# MN42_v2base.net
KiCad netlist of a schematic drawn in EasyEDA Pro
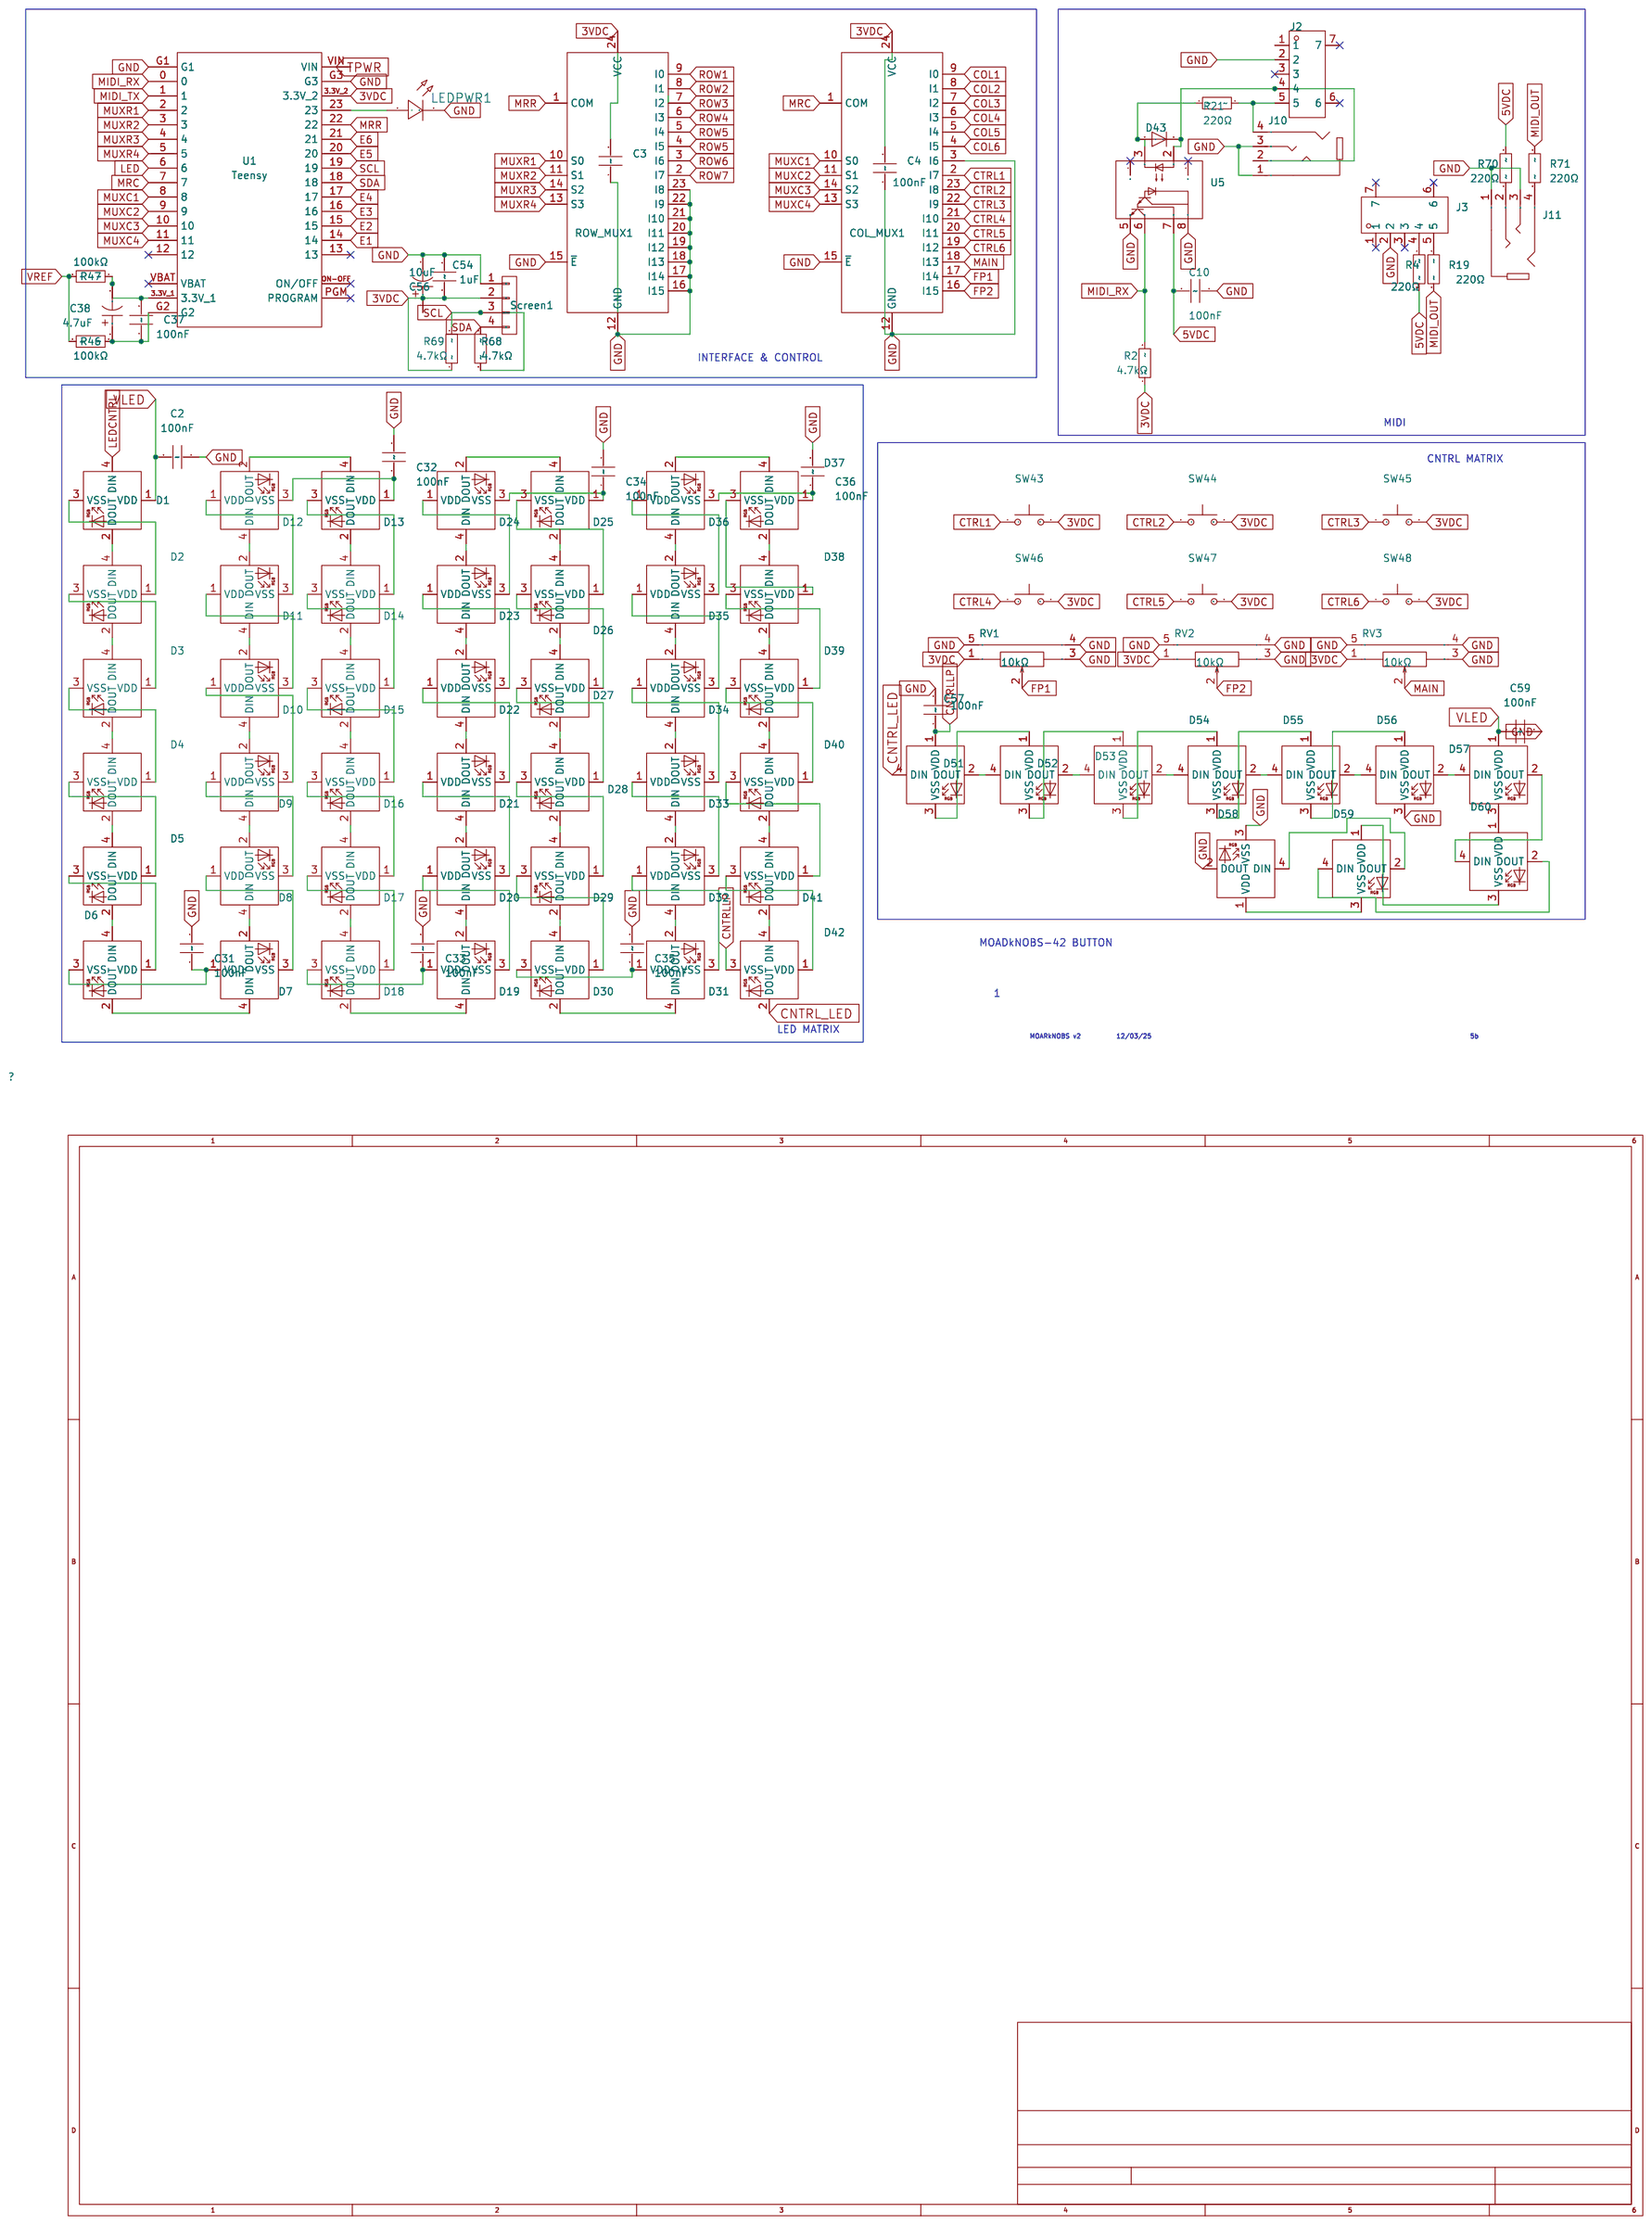
[diagram p0: INTERFACE/LED/MIDI/CNTRL]
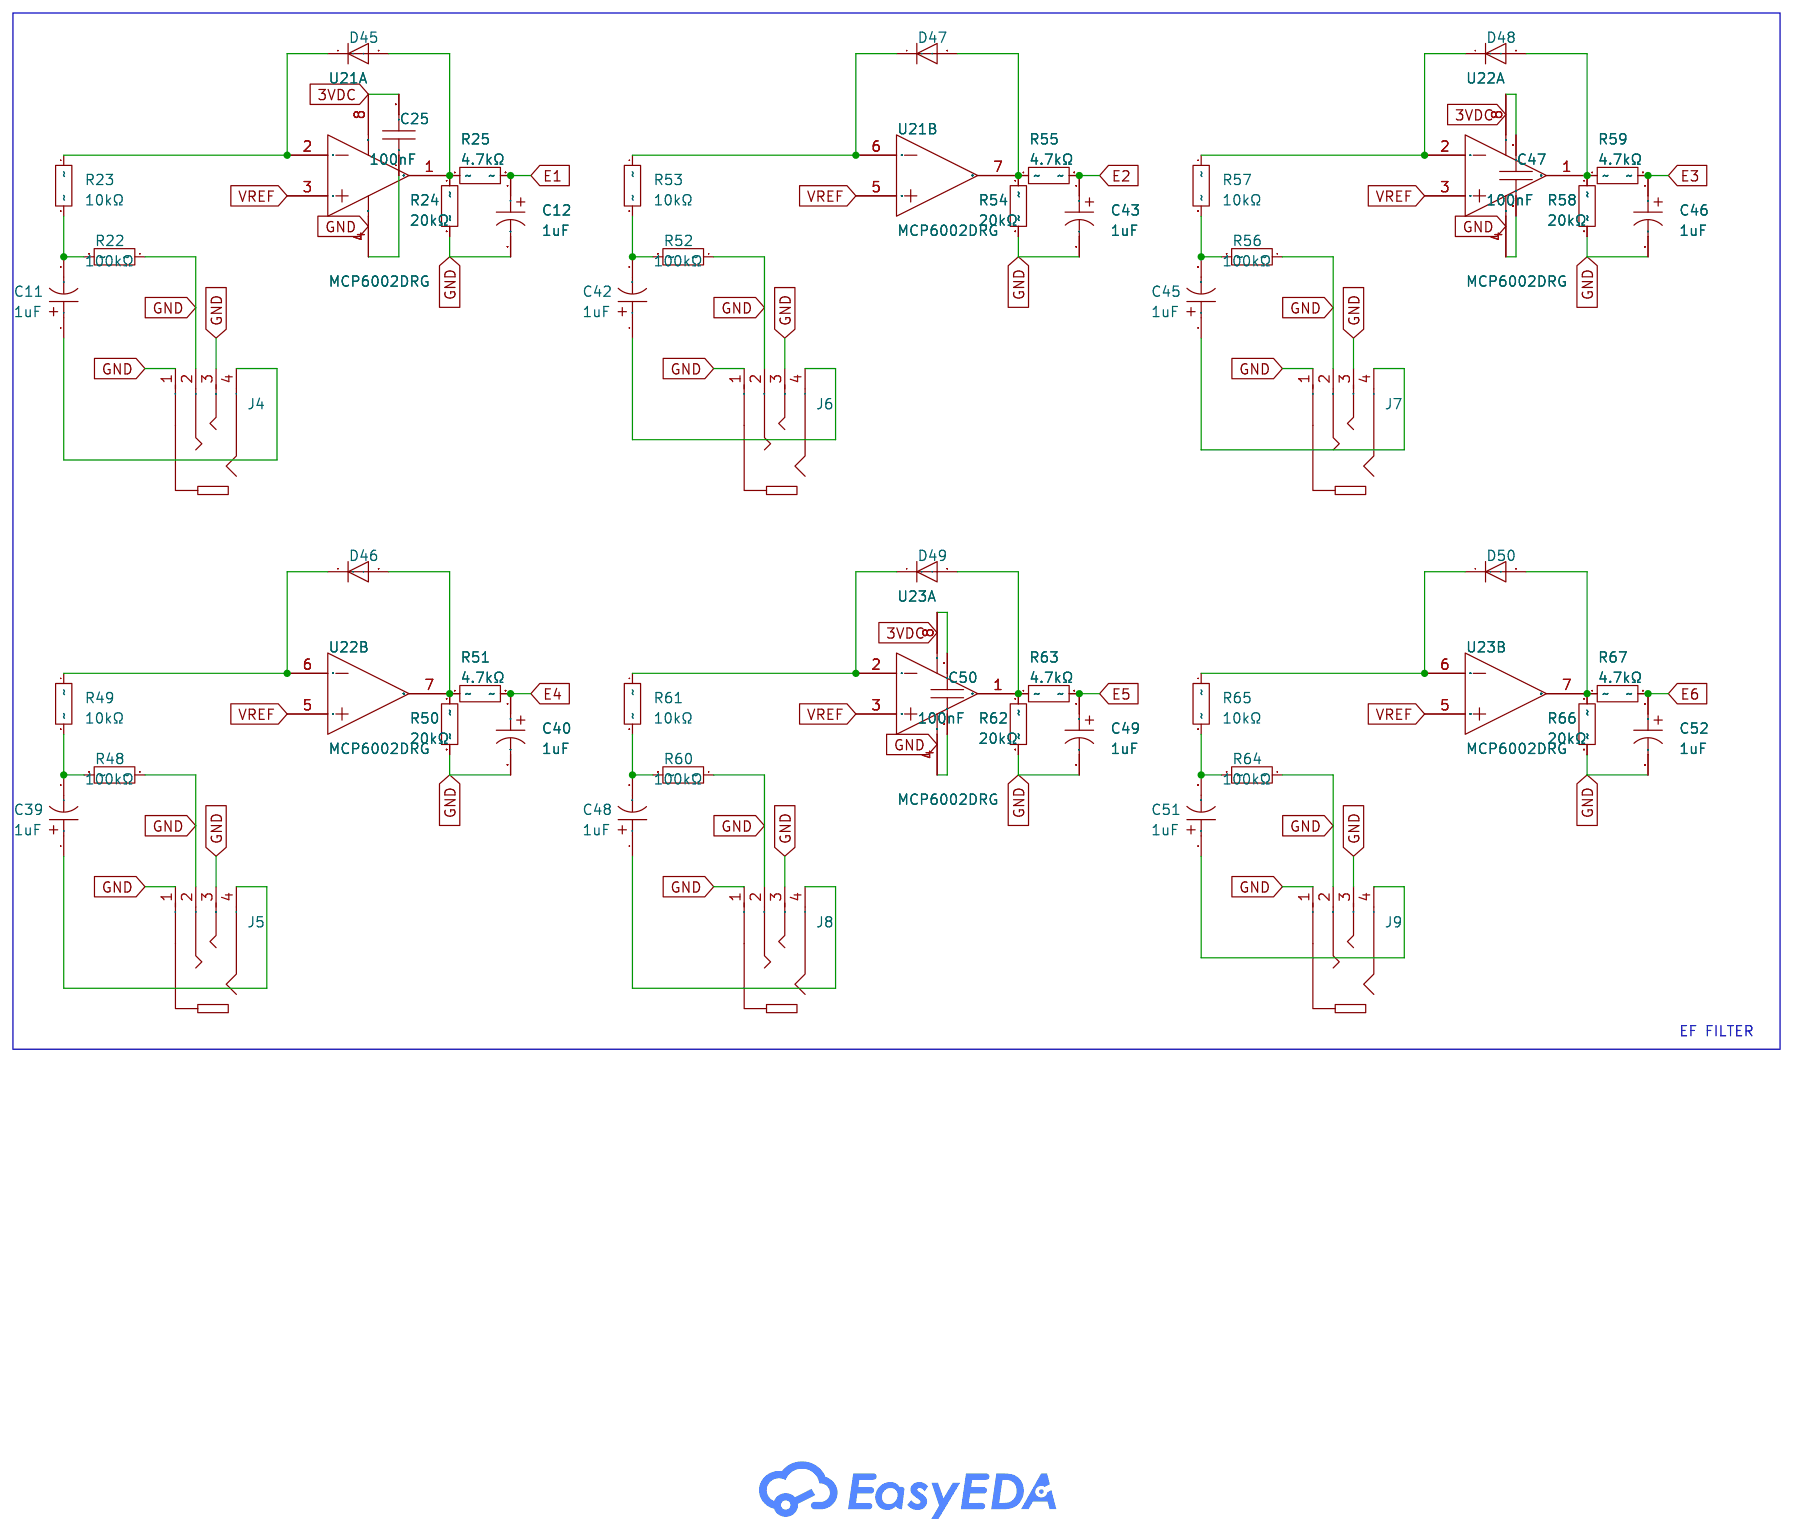
[diagram p1: ENVELOPE]
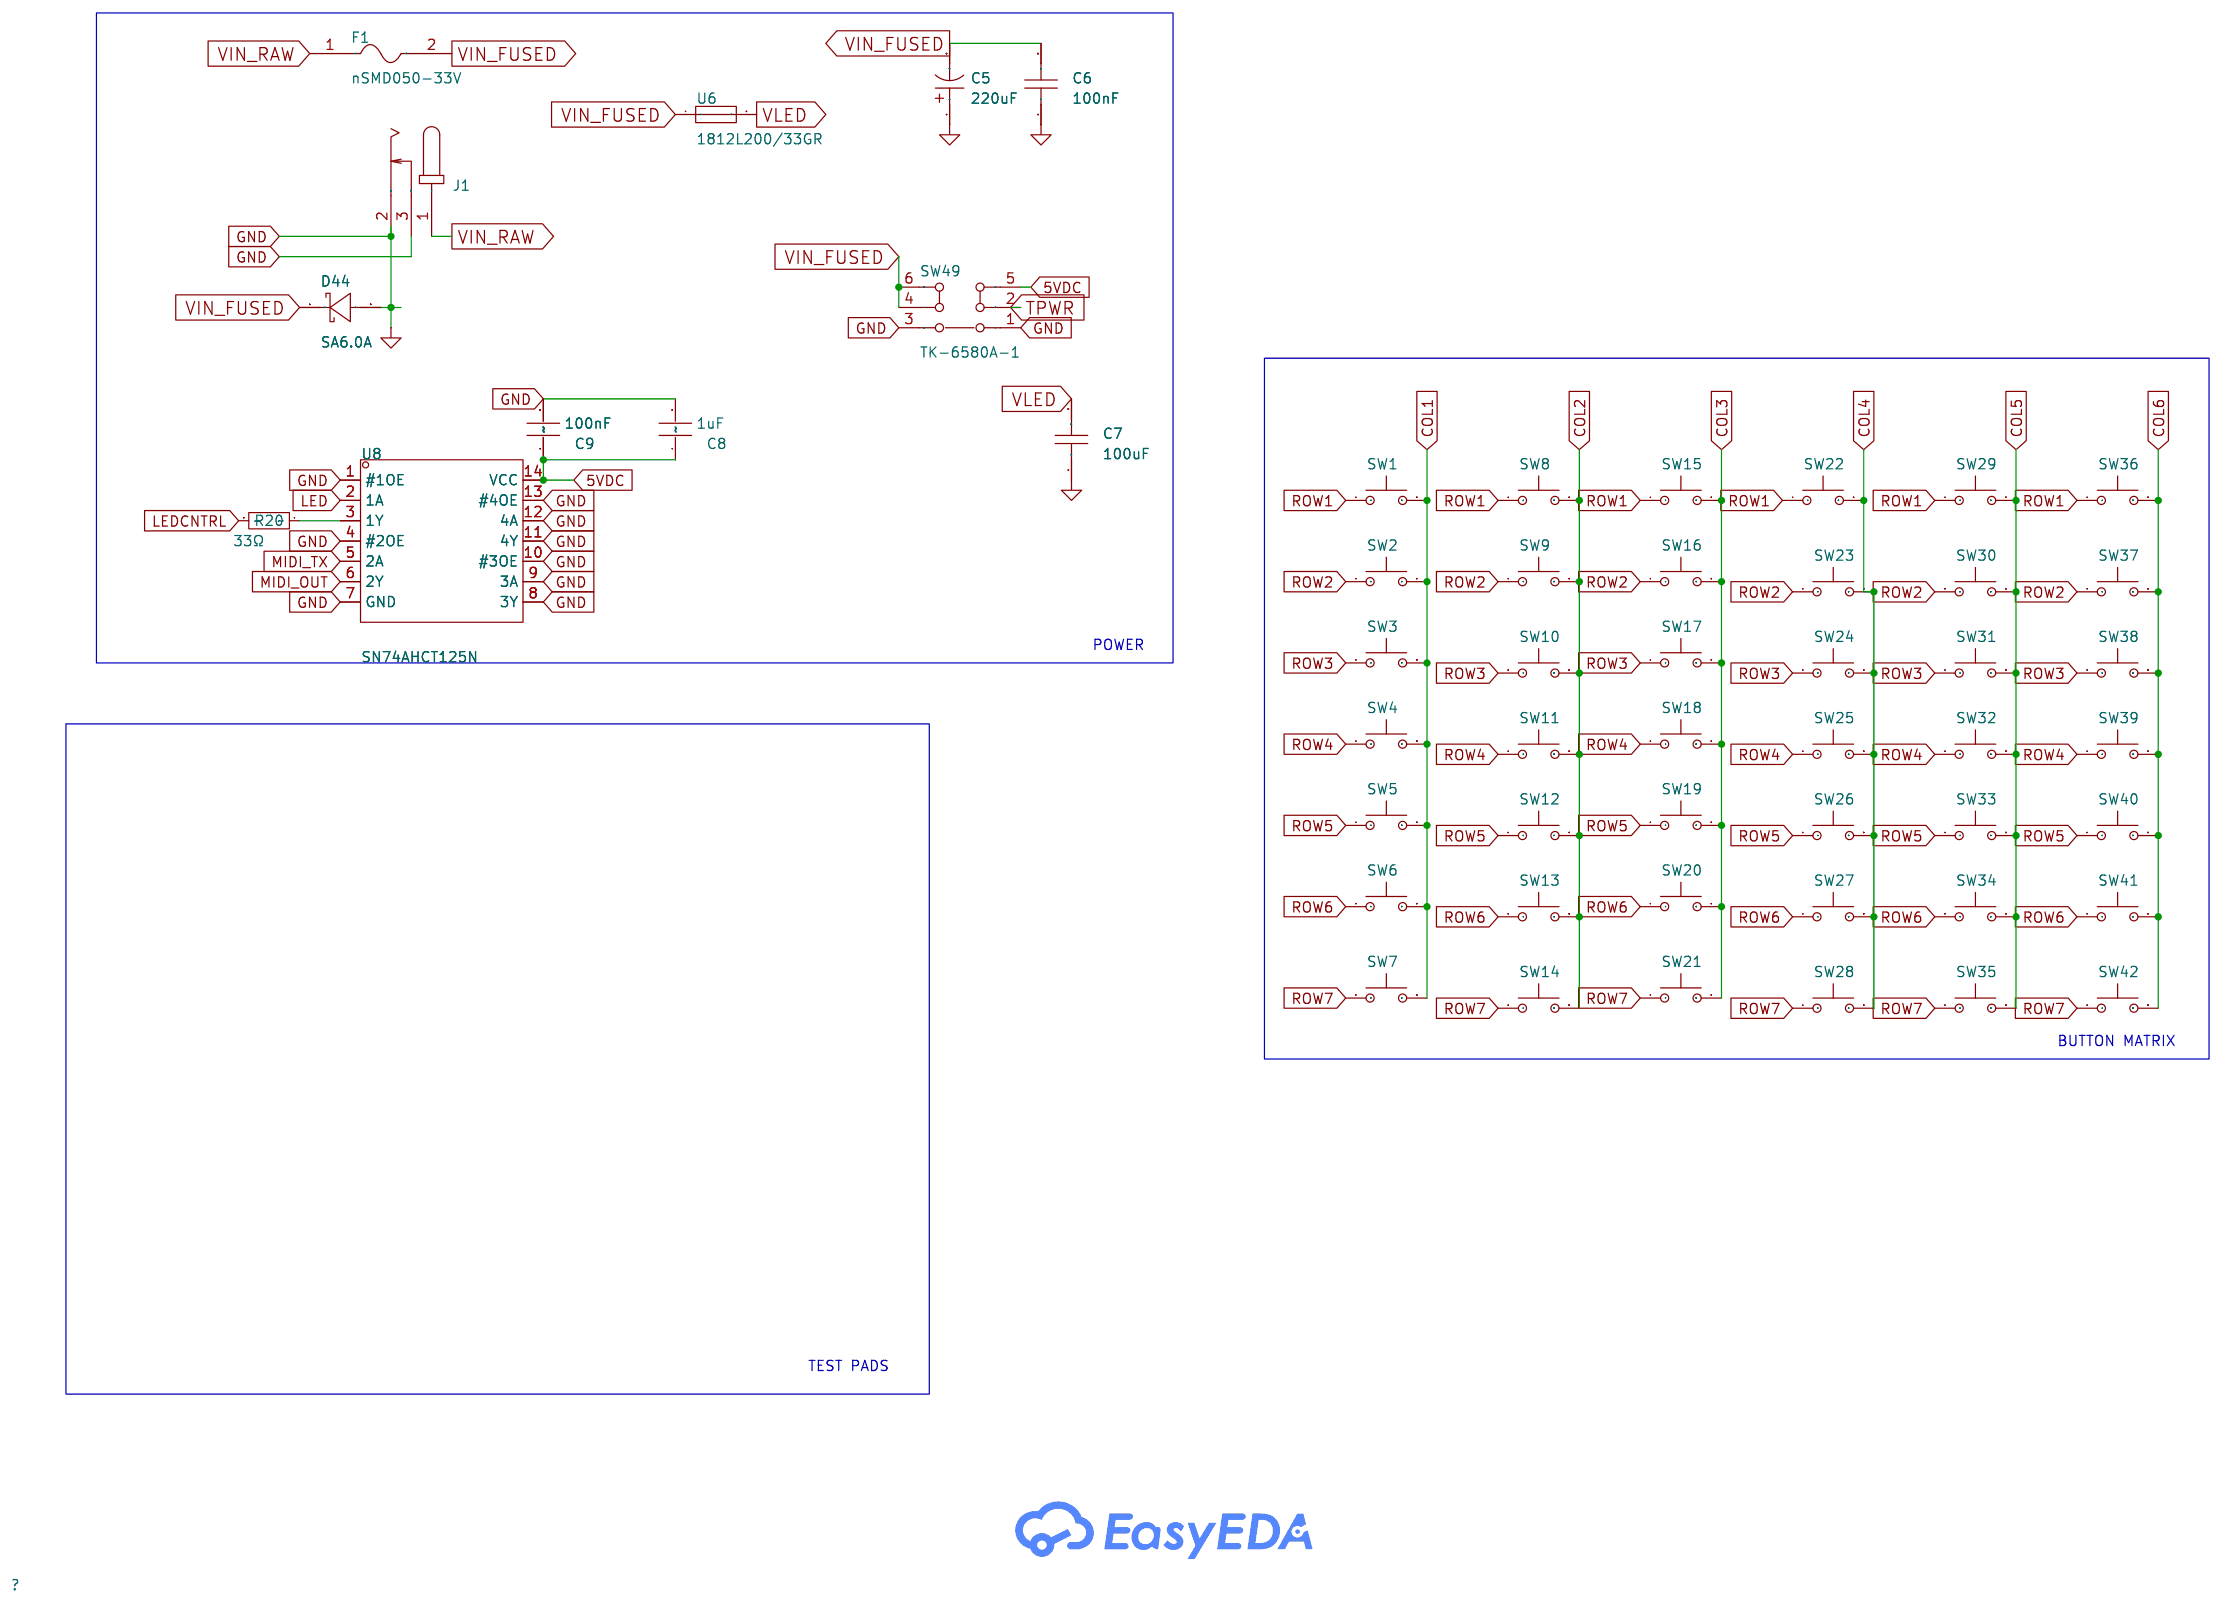
[diagram p2: PWR/BUTTON/TEST]

(export (version "E")
  (design (tool "Eeschema 10.0.6"))
  (components
    (comp (ref "C2")
      (value "100nF")
      (footprint "easyedapro:Capacitor_THT:C_Disc_D3.4mm_W2.1mm_P2.50mm")
      (description "Capacitance:100nF Tolerance:±10% Tolerance:±10% Voltage Rating:63V Temperature Coefficient:-")
      (fields
        (field (name "Manufacturer Part") "CT4G-0805-2X1-63V-0.1μF-K")
        (field (name "Manufacturer") "TORCH(火炬)")
      )
      (libsource (lib "easyedapro") (part "Device_C"))
    )
    (comp (ref "C3")
      (value "100nF")
      (footprint "easyedapro:Capacitor_THT:C_Disc_D3.4mm_W2.1mm_P2.50mm")
      (description "Capacitance:100nF Tolerance:±10% Tolerance:±10% Voltage Rating:63V Temperature Coefficient:-")
      (fields
        (field (name "Manufacturer Part") "CT4G-0805-2X1-63V-0.1μF-K")
        (field (name "Manufacturer") "TORCH(火炬)")
      )
      (libsource (lib "easyedapro") (part "Device_C"))
    )
    (comp (ref "C4")
      (value "100nF")
      (footprint "easyedapro:Capacitor_THT:C_Disc_D3.4mm_W2.1mm_P2.50mm")
      (description "Capacitance:100nF Tolerance:±10% Tolerance:±10% Voltage Rating:63V Temperature Coefficient:-")
      (fields
        (field (name "Manufacturer Part") "CT4G-0805-2X1-63V-0.1μF-K")
        (field (name "Manufacturer") "TORCH(火炬)")
      )
      (libsource (lib "easyedapro") (part "Device_C"))
    )
    (comp (ref "C10")
      (value "100nF")
      (footprint "easyedapro:Capacitor_THT:C_Disc_D3.4mm_W2.1mm_P2.50mm")
      (description "Capacitance:100nF Tolerance:±10% Tolerance:±10% Voltage Rating:63V Temperature Coefficient:-")
      (fields
        (field (name "Manufacturer Part") "CT4G-0805-2X1-63V-0.1μF-K")
        (field (name "Manufacturer") "TORCH(火炬)")
      )
      (libsource (lib "easyedapro") (part "Device_C"))
    )
    (comp (ref "C31")
      (value "100nF")
      (footprint "easyedapro:Capacitor_THT:C_Disc_D3.4mm_W2.1mm_P2.50mm")
      (description "Capacitance:100nF Tolerance:±10% Tolerance:±10% Voltage Rating:63V Temperature Coefficient:-")
      (fields
        (field (name "Manufacturer Part") "CT4G-0805-2X1-63V-0.1μF-K")
        (field (name "Manufacturer") "TORCH(火炬)")
      )
      (libsource (lib "easyedapro") (part "Device_C"))
    )
    (comp (ref "C32")
      (value "100nF")
      (footprint "easyedapro:Capacitor_THT:C_Disc_D3.4mm_W2.1mm_P2.50mm")
      (description "Capacitance:100nF Tolerance:±10% Tolerance:±10% Voltage Rating:63V Temperature Coefficient:-")
      (fields
        (field (name "Manufacturer Part") "CT4G-0805-2X1-63V-0.1μF-K")
        (field (name "Manufacturer") "TORCH(火炬)")
      )
      (libsource (lib "easyedapro") (part "Device_C"))
    )
    (comp (ref "C33")
      (value "100nF")
      (footprint "easyedapro:Capacitor_THT:C_Disc_D3.4mm_W2.1mm_P2.50mm")
      (description "Capacitance:100nF Tolerance:±10% Tolerance:±10% Voltage Rating:63V Temperature Coefficient:-")
      (fields
        (field (name "Manufacturer Part") "CT4G-0805-2X1-63V-0.1μF-K")
        (field (name "Manufacturer") "TORCH(火炬)")
      )
      (libsource (lib "easyedapro") (part "Device_C"))
    )
    (comp (ref "C34")
      (value "100nF")
      (footprint "easyedapro:Capacitor_THT:C_Disc_D3.4mm_W2.1mm_P2.50mm")
      (description "Capacitance:100nF Tolerance:±10% Tolerance:±10% Voltage Rating:63V Temperature Coefficient:-")
      (fields
        (field (name "Manufacturer Part") "CT4G-0805-2X1-63V-0.1μF-K")
        (field (name "Manufacturer") "TORCH(火炬)")
      )
      (libsource (lib "easyedapro") (part "Device_C"))
    )
    (comp (ref "C35")
      (value "100nF")
      (footprint "easyedapro:Capacitor_THT:C_Disc_D3.4mm_W2.1mm_P2.50mm")
      (description "Capacitance:100nF Tolerance:±10% Tolerance:±10% Voltage Rating:63V Temperature Coefficient:-")
      (fields
        (field (name "Manufacturer Part") "CT4G-0805-2X1-63V-0.1μF-K")
        (field (name "Manufacturer") "TORCH(火炬)")
      )
      (libsource (lib "easyedapro") (part "Device_C"))
    )
    (comp (ref "C36")
      (value "100nF")
      (footprint "easyedapro:Capacitor_THT:C_Disc_D3.4mm_W2.1mm_P2.50mm")
      (description "Capacitance:100nF Tolerance:±10% Tolerance:±10% Voltage Rating:63V Temperature Coefficient:-")
      (fields
        (field (name "Manufacturer Part") "CT4G-0805-2X1-63V-0.1μF-K")
        (field (name "Manufacturer") "TORCH(火炬)")
      )
      (libsource (lib "easyedapro") (part "Device_C"))
    )
    (comp (ref "C37")
      (value "100nF")
      (footprint "easyedapro:Capacitor_THT:C_Disc_D3.4mm_W2.1mm_P2.50mm")
      (description "Capacitance:100nF Tolerance:±10% Tolerance:±10% Voltage Rating:63V Temperature Coefficient:-")
      (fields
        (field (name "Manufacturer Part") "CT4G-0805-2X1-63V-0.1μF-K")
        (field (name "Manufacturer") "TORCH(火炬)")
      )
      (libsource (lib "easyedapro") (part "Device_C"))
    )
    (comp (ref "C38")
      (value "4.7uF")
      (footprint "easyedapro:CAP-SMD_BD6.3-L6.6-W6.6-FD")
      (fields (field (name "Manufacturer Part") "189RV0019") (field (name "Manufacturer") "KNSCHA(科尼盛)"))
      (libsource (lib "easyedapro") (part "189RV0019"))
    )
    (comp (ref "C54")
      (value "1uF")
      (footprint "easyedapro:Capacitor_THT:C_Disc_D3.4mm_W2.1mm_P2.50mm")
      (description "Capacitance:100nF Tolerance:±10% Tolerance:±10% Voltage Rating:63V Temperature Coefficient:-")
      (fields
        (field (name "Manufacturer Part") "CT4G-0805-2X1-63V-0.1μF-K")
        (field (name "Manufacturer") "TORCH(火炬)")
      )
      (libsource (lib "easyedapro") (part "Device_C"))
    )
    (comp (ref "C56")
      (value "10uF")
      (footprint "easyedapro:CAP-SMD_BD6.3-L6.6-W6.6-FD")
      (fields (field (name "Manufacturer Part") "189RV0019") (field (name "Manufacturer") "KNSCHA(科尼盛)"))
      (libsource (lib "easyedapro") (part "189RV0019"))
    )
    (comp (ref "C57")
      (value "100nF")
      (footprint "easyedapro:Capacitor_THT:C_Disc_D3.4mm_W2.1mm_P2.50mm")
      (description "Capacitance:100nF Tolerance:±10% Tolerance:±10% Voltage Rating:63V Temperature Coefficient:-")
      (fields
        (field (name "Manufacturer Part") "CT4G-0805-2X1-63V-0.1μF-K")
        (field (name "Manufacturer") "TORCH(火炬)")
      )
      (libsource (lib "easyedapro") (part "Device_C"))
    )
    (comp (ref "C59")
      (value "100nF")
      (footprint "easyedapro:Capacitor_THT:C_Disc_D3.4mm_W2.1mm_P2.50mm")
      (description "Capacitance:100nF Tolerance:±10% Tolerance:±10% Voltage Rating:63V Temperature Coefficient:-")
      (fields
        (field (name "Manufacturer Part") "CT4G-0805-2X1-63V-0.1μF-K")
        (field (name "Manufacturer") "TORCH(火炬)")
      )
      (libsource (lib "easyedapro") (part "Device_C"))
    )
    (comp (ref "COL_MUX1")
      (value "CD74HC4067M96")
      (footprint "easyedapro:Package_SO:SOIC-24W_7.5x15.4mm_P1.27mm")
      (fields (field (name "Manufacturer") "TI(德州仪器)"))
      (libsource (lib "easyedapro") (part "74xx_CD74HC4067M"))
    )
    (comp (ref "D1")
      (value "XL-5050RGBC-WS2812B")
      (footprint "easyedapro:LED_SMD:LED_WS2812B_PLCC4_5.0x5.0mm_P3.2mm")
      (fields (field (name "Manufacturer") "XINGLIGHT(成兴光)"))
      (libsource (lib "easyedapro") (part "LED_WS2812B"))
    )
    (comp (ref "D2")
      (value "XL-5050RGBC-WS2812B")
      (footprint "easyedapro:LED_SMD:LED_WS2812B_PLCC4_5.0x5.0mm_P3.2mm")
      (fields (field (name "Manufacturer") "XINGLIGHT(成兴光)"))
      (libsource (lib "easyedapro") (part "LED_WS2812B"))
    )
    (comp (ref "D3")
      (value "XL-5050RGBC-WS2812B")
      (footprint "easyedapro:LED_SMD:LED_WS2812B_PLCC4_5.0x5.0mm_P3.2mm")
      (fields (field (name "Manufacturer") "XINGLIGHT(成兴光)"))
      (libsource (lib "easyedapro") (part "LED_WS2812B"))
    )
    (comp (ref "D4")
      (value "XL-5050RGBC-WS2812B")
      (footprint "easyedapro:LED_SMD:LED_WS2812B_PLCC4_5.0x5.0mm_P3.2mm")
      (fields (field (name "Manufacturer") "XINGLIGHT(成兴光)"))
      (libsource (lib "easyedapro") (part "LED_WS2812B"))
    )
    (comp (ref "D5")
      (value "XL-5050RGBC-WS2812B")
      (footprint "easyedapro:LED_SMD:LED_WS2812B_PLCC4_5.0x5.0mm_P3.2mm")
      (fields (field (name "Manufacturer") "XINGLIGHT(成兴光)"))
      (libsource (lib "easyedapro") (part "LED_WS2812B"))
    )
    (comp (ref "D6")
      (value "XL-5050RGBC-WS2812B")
      (footprint "easyedapro:LED_SMD:LED_WS2812B_PLCC4_5.0x5.0mm_P3.2mm")
      (fields (field (name "Manufacturer") "XINGLIGHT(成兴光)"))
      (libsource (lib "easyedapro") (part "LED_WS2812B"))
    )
    (comp (ref "D7")
      (value "XL-5050RGBC-WS2812B")
      (footprint "easyedapro:LED_SMD:LED_WS2812B_PLCC4_5.0x5.0mm_P3.2mm")
      (fields (field (name "Manufacturer") "XINGLIGHT(成兴光)"))
      (libsource (lib "easyedapro") (part "LED_WS2812B"))
    )
    (comp (ref "D8")
      (value "XL-5050RGBC-WS2812B")
      (footprint "easyedapro:LED_SMD:LED_WS2812B_PLCC4_5.0x5.0mm_P3.2mm")
      (fields (field (name "Manufacturer") "XINGLIGHT(成兴光)"))
      (libsource (lib "easyedapro") (part "LED_WS2812B"))
    )
    (comp (ref "D9")
      (value "XL-5050RGBC-WS2812B")
      (footprint "easyedapro:LED_SMD:LED_WS2812B_PLCC4_5.0x5.0mm_P3.2mm")
      (fields (field (name "Manufacturer") "XINGLIGHT(成兴光)"))
      (libsource (lib "easyedapro") (part "LED_WS2812B"))
    )
    (comp (ref "D10")
      (value "XL-5050RGBC-WS2812B")
      (footprint "easyedapro:LED_SMD:LED_WS2812B_PLCC4_5.0x5.0mm_P3.2mm")
      (fields (field (name "Manufacturer") "XINGLIGHT(成兴光)"))
      (libsource (lib "easyedapro") (part "LED_WS2812B"))
    )
    (comp (ref "D11")
      (value "XL-5050RGBC-WS2812B")
      (footprint "easyedapro:LED_SMD:LED_WS2812B_PLCC4_5.0x5.0mm_P3.2mm")
      (fields (field (name "Manufacturer") "XINGLIGHT(成兴光)"))
      (libsource (lib "easyedapro") (part "LED_WS2812B"))
    )
    (comp (ref "D12")
      (value "XL-5050RGBC-WS2812B")
      (footprint "easyedapro:LED_SMD:LED_WS2812B_PLCC4_5.0x5.0mm_P3.2mm")
      (fields (field (name "Manufacturer") "XINGLIGHT(成兴光)"))
      (libsource (lib "easyedapro") (part "LED_WS2812B"))
    )
    (comp (ref "D13")
      (value "XL-5050RGBC-WS2812B")
      (footprint "easyedapro:LED_SMD:LED_WS2812B_PLCC4_5.0x5.0mm_P3.2mm")
      (fields (field (name "Manufacturer") "XINGLIGHT(成兴光)"))
      (libsource (lib "easyedapro") (part "LED_WS2812B"))
    )
    (comp (ref "D14")
      (value "XL-5050RGBC-WS2812B")
      (footprint "easyedapro:LED_SMD:LED_WS2812B_PLCC4_5.0x5.0mm_P3.2mm")
      (fields (field (name "Manufacturer") "XINGLIGHT(成兴光)"))
      (libsource (lib "easyedapro") (part "LED_WS2812B"))
    )
    (comp (ref "D15")
      (value "XL-5050RGBC-WS2812B")
      (footprint "easyedapro:LED_SMD:LED_WS2812B_PLCC4_5.0x5.0mm_P3.2mm")
      (fields (field (name "Manufacturer") "XINGLIGHT(成兴光)"))
      (libsource (lib "easyedapro") (part "LED_WS2812B"))
    )
    (comp (ref "D16")
      (value "XL-5050RGBC-WS2812B")
      (footprint "easyedapro:LED_SMD:LED_WS2812B_PLCC4_5.0x5.0mm_P3.2mm")
      (fields (field (name "Manufacturer") "XINGLIGHT(成兴光)"))
      (libsource (lib "easyedapro") (part "LED_WS2812B"))
    )
    (comp (ref "D17")
      (value "XL-5050RGBC-WS2812B")
      (footprint "easyedapro:LED_SMD:LED_WS2812B_PLCC4_5.0x5.0mm_P3.2mm")
      (fields (field (name "Manufacturer") "XINGLIGHT(成兴光)"))
      (libsource (lib "easyedapro") (part "LED_WS2812B"))
    )
    (comp (ref "D18")
      (value "XL-5050RGBC-WS2812B")
      (footprint "easyedapro:LED_SMD:LED_WS2812B_PLCC4_5.0x5.0mm_P3.2mm")
      (fields (field (name "Manufacturer") "XINGLIGHT(成兴光)"))
      (libsource (lib "easyedapro") (part "LED_WS2812B"))
    )
    (comp (ref "D19")
      (value "XL-5050RGBC-WS2812B")
      (footprint "easyedapro:LED_SMD:LED_WS2812B_PLCC4_5.0x5.0mm_P3.2mm")
      (fields (field (name "Manufacturer") "XINGLIGHT(成兴光)"))
      (libsource (lib "easyedapro") (part "LED_WS2812B"))
    )
    (comp (ref "D20")
      (value "XL-5050RGBC-WS2812B")
      (footprint "easyedapro:LED_SMD:LED_WS2812B_PLCC4_5.0x5.0mm_P3.2mm")
      (fields (field (name "Manufacturer") "XINGLIGHT(成兴光)"))
      (libsource (lib "easyedapro") (part "LED_WS2812B"))
    )
    (comp (ref "D21")
      (value "XL-5050RGBC-WS2812B")
      (footprint "easyedapro:LED_SMD:LED_WS2812B_PLCC4_5.0x5.0mm_P3.2mm")
      (fields (field (name "Manufacturer") "XINGLIGHT(成兴光)"))
      (libsource (lib "easyedapro") (part "LED_WS2812B"))
    )
    (comp (ref "D22")
      (value "XL-5050RGBC-WS2812B")
      (footprint "easyedapro:LED_SMD:LED_WS2812B_PLCC4_5.0x5.0mm_P3.2mm")
      (fields (field (name "Manufacturer") "XINGLIGHT(成兴光)"))
      (libsource (lib "easyedapro") (part "LED_WS2812B"))
    )
    (comp (ref "D23")
      (value "XL-5050RGBC-WS2812B")
      (footprint "easyedapro:LED_SMD:LED_WS2812B_PLCC4_5.0x5.0mm_P3.2mm")
      (fields (field (name "Manufacturer") "XINGLIGHT(成兴光)"))
      (libsource (lib "easyedapro") (part "LED_WS2812B"))
    )
    (comp (ref "D24")
      (value "XL-5050RGBC-WS2812B")
      (footprint "easyedapro:LED_SMD:LED_WS2812B_PLCC4_5.0x5.0mm_P3.2mm")
      (fields (field (name "Manufacturer") "XINGLIGHT(成兴光)"))
      (libsource (lib "easyedapro") (part "LED_WS2812B"))
    )
    (comp (ref "D25")
      (value "XL-5050RGBC-WS2812B")
      (footprint "easyedapro:LED_SMD:LED_WS2812B_PLCC4_5.0x5.0mm_P3.2mm")
      (fields (field (name "Manufacturer") "XINGLIGHT(成兴光)"))
      (libsource (lib "easyedapro") (part "LED_WS2812B"))
    )
    (comp (ref "D26")
      (value "XL-5050RGBC-WS2812B")
      (footprint "easyedapro:LED_SMD:LED_WS2812B_PLCC4_5.0x5.0mm_P3.2mm")
      (fields (field (name "Manufacturer") "XINGLIGHT(成兴光)"))
      (libsource (lib "easyedapro") (part "LED_WS2812B"))
    )
    (comp (ref "D27")
      (value "XL-5050RGBC-WS2812B")
      (footprint "easyedapro:LED_SMD:LED_WS2812B_PLCC4_5.0x5.0mm_P3.2mm")
      (fields (field (name "Manufacturer") "XINGLIGHT(成兴光)"))
      (libsource (lib "easyedapro") (part "LED_WS2812B"))
    )
    (comp (ref "D28")
      (value "XL-5050RGBC-WS2812B")
      (footprint "easyedapro:LED_SMD:LED_WS2812B_PLCC4_5.0x5.0mm_P3.2mm")
      (fields (field (name "Manufacturer") "XINGLIGHT(成兴光)"))
      (libsource (lib "easyedapro") (part "LED_WS2812B"))
    )
    (comp (ref "D29")
      (value "XL-5050RGBC-WS2812B")
      (footprint "easyedapro:LED_SMD:LED_WS2812B_PLCC4_5.0x5.0mm_P3.2mm")
      (fields (field (name "Manufacturer") "XINGLIGHT(成兴光)"))
      (libsource (lib "easyedapro") (part "LED_WS2812B"))
    )
    (comp (ref "D30")
      (value "XL-5050RGBC-WS2812B")
      (footprint "easyedapro:LED_SMD:LED_WS2812B_PLCC4_5.0x5.0mm_P3.2mm")
      (fields (field (name "Manufacturer") "XINGLIGHT(成兴光)"))
      (libsource (lib "easyedapro") (part "LED_WS2812B"))
    )
    (comp (ref "D31")
      (value "XL-5050RGBC-WS2812B")
      (footprint "easyedapro:LED_SMD:LED_WS2812B_PLCC4_5.0x5.0mm_P3.2mm")
      (fields (field (name "Manufacturer") "XINGLIGHT(成兴光)"))
      (libsource (lib "easyedapro") (part "LED_WS2812B"))
    )
    (comp (ref "D32")
      (value "XL-5050RGBC-WS2812B")
      (footprint "easyedapro:LED_SMD:LED_WS2812B_PLCC4_5.0x5.0mm_P3.2mm")
      (fields (field (name "Manufacturer") "XINGLIGHT(成兴光)"))
      (libsource (lib "easyedapro") (part "LED_WS2812B"))
    )
    (comp (ref "D33")
      (value "XL-5050RGBC-WS2812B")
      (footprint "easyedapro:LED_SMD:LED_WS2812B_PLCC4_5.0x5.0mm_P3.2mm")
      (fields (field (name "Manufacturer") "XINGLIGHT(成兴光)"))
      (libsource (lib "easyedapro") (part "LED_WS2812B"))
    )
    (comp (ref "D34")
      (value "XL-5050RGBC-WS2812B")
      (footprint "easyedapro:LED_SMD:LED_WS2812B_PLCC4_5.0x5.0mm_P3.2mm")
      (fields (field (name "Manufacturer") "XINGLIGHT(成兴光)"))
      (libsource (lib "easyedapro") (part "LED_WS2812B"))
    )
    (comp (ref "D35")
      (value "XL-5050RGBC-WS2812B")
      (footprint "easyedapro:LED_SMD:LED_WS2812B_PLCC4_5.0x5.0mm_P3.2mm")
      (fields (field (name "Manufacturer") "XINGLIGHT(成兴光)"))
      (libsource (lib "easyedapro") (part "LED_WS2812B"))
    )
    (comp (ref "D36")
      (value "XL-5050RGBC-WS2812B")
      (footprint "easyedapro:LED_SMD:LED_WS2812B_PLCC4_5.0x5.0mm_P3.2mm")
      (fields (field (name "Manufacturer") "XINGLIGHT(成兴光)"))
      (libsource (lib "easyedapro") (part "LED_WS2812B"))
    )
    (comp (ref "D37")
      (value "XL-5050RGBC-WS2812B")
      (footprint "easyedapro:LED_SMD:LED_WS2812B_PLCC4_5.0x5.0mm_P3.2mm")
      (fields (field (name "Manufacturer") "XINGLIGHT(成兴光)"))
      (libsource (lib "easyedapro") (part "LED_WS2812B"))
    )
    (comp (ref "D38")
      (value "XL-5050RGBC-WS2812B")
      (footprint "easyedapro:LED_SMD:LED_WS2812B_PLCC4_5.0x5.0mm_P3.2mm")
      (fields (field (name "Manufacturer") "XINGLIGHT(成兴光)"))
      (libsource (lib "easyedapro") (part "LED_WS2812B"))
    )
    (comp (ref "D39")
      (value "XL-5050RGBC-WS2812B")
      (footprint "easyedapro:LED_SMD:LED_WS2812B_PLCC4_5.0x5.0mm_P3.2mm")
      (fields (field (name "Manufacturer") "XINGLIGHT(成兴光)"))
      (libsource (lib "easyedapro") (part "LED_WS2812B"))
    )
    (comp (ref "D40")
      (value "XL-5050RGBC-WS2812B")
      (footprint "easyedapro:LED_SMD:LED_WS2812B_PLCC4_5.0x5.0mm_P3.2mm")
      (fields (field (name "Manufacturer") "XINGLIGHT(成兴光)"))
      (libsource (lib "easyedapro") (part "LED_WS2812B"))
    )
    (comp (ref "D41")
      (value "XL-5050RGBC-WS2812B")
      (footprint "easyedapro:LED_SMD:LED_WS2812B_PLCC4_5.0x5.0mm_P3.2mm")
      (fields (field (name "Manufacturer") "XINGLIGHT(成兴光)"))
      (libsource (lib "easyedapro") (part "LED_WS2812B"))
    )
    (comp (ref "D42")
      (value "XL-5050RGBC-WS2812B")
      (footprint "easyedapro:LED_SMD:LED_WS2812B_PLCC4_5.0x5.0mm_P3.2mm")
      (fields (field (name "Manufacturer") "XINGLIGHT(成兴光)"))
      (libsource (lib "easyedapro") (part "LED_WS2812B"))
    )
    (comp (ref "D43")
      (value "1N4148PF")
      (footprint "easyedapro:Diode_THT:D_DO-35_SOD27_P7.62mm_Horizontal")
      (fields (field (name "Manufacturer") "ST(先科)"))
      (libsource (lib "easyedapro") (part "Diode_1N4148"))
    )
    (comp (ref "D51")
      (value "XL-5050RGBC-WS2812B")
      (footprint "easyedapro:LED_SMD:LED_WS2812B_PLCC4_5.0x5.0mm_P3.2mm")
      (fields (field (name "Manufacturer") "XINGLIGHT(成兴光)"))
      (libsource (lib "easyedapro") (part "LED_WS2812B"))
    )
    (comp (ref "D52")
      (value "XL-5050RGBC-WS2812B")
      (footprint "easyedapro:LED_SMD:LED_WS2812B_PLCC4_5.0x5.0mm_P3.2mm")
      (fields (field (name "Manufacturer") "XINGLIGHT(成兴光)"))
      (libsource (lib "easyedapro") (part "LED_WS2812B"))
    )
    (comp (ref "D53")
      (value "XL-5050RGBC-WS2812B")
      (footprint "easyedapro:LED_SMD:LED_WS2812B_PLCC4_5.0x5.0mm_P3.2mm")
      (fields (field (name "Manufacturer") "XINGLIGHT(成兴光)"))
      (libsource (lib "easyedapro") (part "LED_WS2812B"))
    )
    (comp (ref "D54")
      (value "XL-5050RGBC-WS2812B")
      (footprint "easyedapro:LED_SMD:LED_WS2812B_PLCC4_5.0x5.0mm_P3.2mm")
      (fields (field (name "Manufacturer") "XINGLIGHT(成兴光)"))
      (libsource (lib "easyedapro") (part "LED_WS2812B"))
    )
    (comp (ref "D55")
      (value "XL-5050RGBC-WS2812B")
      (footprint "easyedapro:LED_SMD:LED_WS2812B_PLCC4_5.0x5.0mm_P3.2mm")
      (fields (field (name "Manufacturer") "XINGLIGHT(成兴光)"))
      (libsource (lib "easyedapro") (part "LED_WS2812B"))
    )
    (comp (ref "D56")
      (value "XL-5050RGBC-WS2812B")
      (footprint "easyedapro:LED_SMD:LED_WS2812B_PLCC4_5.0x5.0mm_P3.2mm")
      (fields (field (name "Manufacturer") "XINGLIGHT(成兴光)"))
      (libsource (lib "easyedapro") (part "LED_WS2812B"))
    )
    (comp (ref "D57")
      (value "XL-5050RGBC-WS2812B")
      (footprint "easyedapro:LED_SMD:LED_WS2812B_PLCC4_5.0x5.0mm_P3.2mm")
      (fields (field (name "Manufacturer") "XINGLIGHT(成兴光)"))
      (libsource (lib "easyedapro") (part "LED_WS2812B"))
    )
    (comp (ref "D58")
      (value "XL-5050RGBC-WS2812B")
      (footprint "easyedapro:LED_SMD:LED_WS2812B_PLCC4_5.0x5.0mm_P3.2mm")
      (fields (field (name "Manufacturer") "XINGLIGHT(成兴光)"))
      (libsource (lib "easyedapro") (part "LED_WS2812B"))
    )
    (comp (ref "D59")
      (value "XL-5050RGBC-WS2812B")
      (footprint "easyedapro:LED_SMD:LED_WS2812B_PLCC4_5.0x5.0mm_P3.2mm")
      (fields (field (name "Manufacturer") "XINGLIGHT(成兴光)"))
      (libsource (lib "easyedapro") (part "LED_WS2812B"))
    )
    (comp (ref "D60")
      (value "XL-5050RGBC-WS2812B")
      (footprint "easyedapro:LED_SMD:LED_WS2812B_PLCC4_5.0x5.0mm_P3.2mm")
      (fields (field (name "Manufacturer") "XINGLIGHT(成兴光)"))
      (libsource (lib "easyedapro") (part "LED_WS2812B"))
    )
    (comp (ref "J2")
      (value "DIN-504B-M10")
      (footprint "easyedapro:CONN-TH_DIN-504B-M10")
      (fields (field (name "Manufacturer") "HOOYA(皓宇电子)"))
      (libsource (lib "easyedapro") (part "DIN-504B-M10"))
    )
    (comp (ref "J3")
      (value "DIN-504B-M10")
      (footprint "easyedapro:CONN-TH_DIN-504B-M10")
      (fields (field (name "Manufacturer") "HOOYA(皓宇电子)"))
      (libsource (lib "easyedapro") (part "DIN-504B-M10"))
    )
    (comp (ref "J10")
      (value "HC-PJ-320A")
      (footprint "easyedapro:AUDIO-SMD_HC-PJ-320A")
      (fields (field (name "Manufacturer") "HC(虹成电子)"))
      (libsource (lib "easyedapro") (part "HC-PJ-320A"))
    )
    (comp (ref "J11")
      (value "HC-PJ-320A")
      (footprint "easyedapro:AUDIO-SMD_HC-PJ-320A")
      (fields (field (name "Manufacturer") "HC(虹成电子)"))
      (libsource (lib "easyedapro") (part "HC-PJ-320A"))
    )
    (comp (ref "LEDPWR1")
      (value "~")
      (footprint "easyedapro:LED_0603")
      (libsource (lib "easyedapro") (part "LED_R"))
    )
    (comp (ref "R2")
      (value "4.7kΩ")
      (footprint "easyedapro:Resistor_THT:R_Axial_DIN0204_L3.6mm_D1.6mm_P2.54mm_Vertical")
      (fields
        (field (name "Manufacturer Part") "RN 1/8W 4K7 F T/B A1")
        (field (name "Manufacturer") "Tyohm(幸亚电阻)")
      )
      (libsource (lib "easyedapro") (part "Device_R"))
    )
    (comp (ref "R4")
      (value "220Ω")
      (footprint "easyedapro:Resistor_THT:R_Axial_DIN0204_L3.6mm_D1.6mm_P2.54mm_Vertical")
      (fields
        (field (name "Manufacturer Part") "RN 1/8W 220R F T/B A1")
        (field (name "Manufacturer") "Tyohm(幸亚电阻)")
      )
      (libsource (lib "easyedapro") (part "Device_R"))
    )
    (comp (ref "R19")
      (value "220Ω")
      (footprint "easyedapro:Resistor_THT:R_Axial_DIN0204_L3.6mm_D1.6mm_P2.54mm_Vertical")
      (fields
        (field (name "Manufacturer Part") "RN 1/8W 220R F T/B A1")
        (field (name "Manufacturer") "Tyohm(幸亚电阻)")
      )
      (libsource (lib "easyedapro") (part "Device_R"))
    )
    (comp (ref "R21")
      (value "220Ω")
      (footprint "easyedapro:Resistor_THT:R_Axial_DIN0204_L3.6mm_D1.6mm_P2.54mm_Vertical")
      (fields
        (field (name "Manufacturer Part") "RN 1/8W 220R F T/B A1")
        (field (name "Manufacturer") "Tyohm(幸亚电阻)")
      )
      (libsource (lib "easyedapro") (part "Device_R"))
    )
    (comp (ref "R46")
      (value "100kΩ")
      (footprint "easyedapro:Resistor_THT:R_Axial_DIN0204_L3.6mm_D1.6mm_P2.54mm_Vertical")
      (fields
        (field (name "Manufacturer Part") "RN1/8W10KFT/BA1")
        (field (name "Manufacturer") "Tyohm(幸亚电阻)")
      )
      (libsource (lib "easyedapro") (part "Device_R"))
    )
    (comp (ref "R47")
      (value "100kΩ")
      (footprint "easyedapro:Resistor_THT:R_Axial_DIN0204_L3.6mm_D1.6mm_P2.54mm_Vertical")
      (fields
        (field (name "Manufacturer Part") "RN1/8W10KFT/BA1")
        (field (name "Manufacturer") "Tyohm(幸亚电阻)")
      )
      (libsource (lib "easyedapro") (part "Device_R"))
    )
    (comp (ref "R68")
      (value "4.7kΩ")
      (footprint "easyedapro:Resistor_THT:R_Axial_DIN0204_L3.6mm_D1.6mm_P2.54mm_Vertical")
      (fields
        (field (name "Manufacturer Part") "RN 1/8W 4K7 F T/B A1")
        (field (name "Manufacturer") "Tyohm(幸亚电阻)")
      )
      (libsource (lib "easyedapro") (part "Device_R"))
    )
    (comp (ref "R69")
      (value "4.7kΩ")
      (footprint "easyedapro:Resistor_THT:R_Axial_DIN0204_L3.6mm_D1.6mm_P2.54mm_Vertical")
      (fields
        (field (name "Manufacturer Part") "RN 1/8W 4K7 F T/B A1")
        (field (name "Manufacturer") "Tyohm(幸亚电阻)")
      )
      (libsource (lib "easyedapro") (part "Device_R"))
    )
    (comp (ref "R70")
      (value "220Ω")
      (footprint "easyedapro:Resistor_THT:R_Axial_DIN0204_L3.6mm_D1.6mm_P2.54mm_Vertical")
      (fields
        (field (name "Manufacturer Part") "RN 1/8W 220R F T/B A1")
        (field (name "Manufacturer") "Tyohm(幸亚电阻)")
      )
      (libsource (lib "easyedapro") (part "Device_R"))
    )
    (comp (ref "R71")
      (value "220Ω")
      (footprint "easyedapro:Resistor_THT:R_Axial_DIN0204_L3.6mm_D1.6mm_P2.54mm_Vertical")
      (fields
        (field (name "Manufacturer Part") "RN 1/8W 220R F T/B A1")
        (field (name "Manufacturer") "Tyohm(幸亚电阻)")
      )
      (libsource (lib "easyedapro") (part "Device_R"))
    )
    (comp (ref "ROW_MUX1")
      (value "CD74HC4067M96")
      (footprint "easyedapro:Package_SO:SOIC-24W_7.5x15.4mm_P1.27mm")
      (fields (field (name "Manufacturer") "TI(德州仪器)"))
      (libsource (lib "easyedapro") (part "74xx_CD74HC4067M"))
    )
    (comp (ref "RV1")
      (value "10kΩ")
      (footprint "easyedapro:RES-ADJ-TH_RK09K1130A5R")
      (description "Resistance: Tolerance:±20% Tolerance:±20%")
      (fields
        (field (name "Manufacturer Part") "RK09K1130A5R")
        (field (name "Manufacturer") "ALPSALPINE(阿尔卑斯阿尔派)")
      )
      (libsource (lib "easyedapro") (part "RK09K1130A5R"))
    )
    (comp (ref "RV2")
      (value "10kΩ")
      (footprint "easyedapro:RES-ADJ-TH_RK09K1130A5R")
      (description "Resistance: Tolerance:±20% Tolerance:±20%")
      (fields
        (field (name "Manufacturer Part") "RK09K1130A5R")
        (field (name "Manufacturer") "ALPSALPINE(阿尔卑斯阿尔派)")
      )
      (libsource (lib "easyedapro") (part "RK09K1130A5R"))
    )
    (comp (ref "RV3")
      (value "10kΩ")
      (footprint "easyedapro:RES-ADJ-TH_RK09K1130A5R")
      (description "Resistance: Tolerance:±20% Tolerance:±20%")
      (fields
        (field (name "Manufacturer Part") "RK09K1130A5R")
        (field (name "Manufacturer") "ALPSALPINE(阿尔卑斯阿尔派)")
      )
      (libsource (lib "easyedapro") (part "RK09K1130A5R"))
    )
    (comp (ref "Screen1")
      (value "HS96L03W2C03")
      (footprint "easyedapro:Connector_JST:JST_EH_S4B-EH_1x04_P2.50mm_Horizontal")
      (fields (field (name "Manufacturer") "HS(汉昇)"))
      (libsource (lib "easyedapro") (part "Connector_Generic_Conn_01x04"))
    )
    (comp (ref "SW43")
      (value "HX B3F-4055-Y")
      (footprint "easyedapro:Button_Switch_SMD:SW_SPST_PTS645")
      (fields (field (name "Manufacturer") "hanxia(韩下)"))
      (libsource (lib "easyedapro") (part "Switch_SW_Push"))
    )
    (comp (ref "SW44")
      (value "HX B3F-4055-Y")
      (footprint "easyedapro:Button_Switch_SMD:SW_SPST_PTS645")
      (fields (field (name "Manufacturer") "hanxia(韩下)"))
      (libsource (lib "easyedapro") (part "Switch_SW_Push"))
    )
    (comp (ref "SW45")
      (value "HX B3F-4055-Y")
      (footprint "easyedapro:Button_Switch_SMD:SW_SPST_PTS645")
      (fields (field (name "Manufacturer") "hanxia(韩下)"))
      (libsource (lib "easyedapro") (part "Switch_SW_Push"))
    )
    (comp (ref "SW46")
      (value "HX B3F-4055-Y")
      (footprint "easyedapro:Button_Switch_SMD:SW_SPST_PTS645")
      (fields (field (name "Manufacturer") "hanxia(韩下)"))
      (libsource (lib "easyedapro") (part "Switch_SW_Push"))
    )
    (comp (ref "SW47")
      (value "HX B3F-4055-Y")
      (footprint "easyedapro:Button_Switch_SMD:SW_SPST_PTS645")
      (fields (field (name "Manufacturer") "hanxia(韩下)"))
      (libsource (lib "easyedapro") (part "Switch_SW_Push"))
    )
    (comp (ref "SW48")
      (value "HX B3F-4055-Y")
      (footprint "easyedapro:Button_Switch_SMD:SW_SPST_PTS645")
      (fields (field (name "Manufacturer") "hanxia(韩下)"))
      (libsource (lib "easyedapro") (part "Switch_SW_Push"))
    )
    (comp (ref "U1")
      (value "Teensy")
      (footprint "easyedapro:teensy 4.0:MODULE_DEV-15583")
      (libsource (lib "easyedapro") (part "teensy40_DEV-15583"))
    )
    (comp (ref "U5")
      (value "6N138")
      (footprint "easyedapro:Package_DIP:DIP-8_W7.62mm")
      (fields (field (name "Manufacturer") "ISOCOM(英国安数光)"))
      (libsource (lib "easyedapro") (part "Isolator_6N138"))
    )
    (comp (ref "C11")
      (value "1uF")
      (footprint "easyedapro:CAP-SMD_BD6.3-L6.6-W6.6-FD")
      (fields (field (name "Manufacturer Part") "189RV0019") (field (name "Manufacturer") "KNSCHA(科尼盛)"))
      (libsource (lib "easyedapro") (part "189RV0019"))
    )
    (comp (ref "C12")
      (value "1uF")
      (footprint "easyedapro:CAP-SMD_BD6.3-L6.6-W6.6-FD")
      (fields (field (name "Manufacturer Part") "189RV0019") (field (name "Manufacturer") "KNSCHA(科尼盛)"))
      (libsource (lib "easyedapro") (part "189RV0019"))
    )
    (comp (ref "C25")
      (value "100nF")
      (footprint "easyedapro:CAP-TH_L5.0-W2.5-P5.00-D1.0")
      (fields
        (field (name "Manufacturer Part") "CC1H104MC1FD3F6C10MF")
        (field (name "Manufacturer") "Dersonic(德尔创)")
      )
      (libsource (lib "easyedapro") (part "CC1H104MC1FD3F6C10MF"))
    )
    (comp (ref "C39")
      (value "1uF")
      (footprint "easyedapro:CAP-SMD_BD6.3-L6.6-W6.6-FD")
      (fields (field (name "Manufacturer Part") "189RV0019") (field (name "Manufacturer") "KNSCHA(科尼盛)"))
      (libsource (lib "easyedapro") (part "189RV0019"))
    )
    (comp (ref "C40")
      (value "1uF")
      (footprint "easyedapro:CAP-SMD_BD6.3-L6.6-W6.6-FD")
      (fields (field (name "Manufacturer Part") "189RV0019") (field (name "Manufacturer") "KNSCHA(科尼盛)"))
      (libsource (lib "easyedapro") (part "189RV0019"))
    )
    (comp (ref "C42")
      (value "1uF")
      (footprint "easyedapro:CAP-SMD_BD6.3-L6.6-W6.6-FD")
      (fields (field (name "Manufacturer Part") "189RV0019") (field (name "Manufacturer") "KNSCHA(科尼盛)"))
      (libsource (lib "easyedapro") (part "189RV0019"))
    )
    (comp (ref "C43")
      (value "1uF")
      (footprint "easyedapro:CAP-SMD_BD6.3-L6.6-W6.6-FD")
      (fields (field (name "Manufacturer Part") "189RV0019") (field (name "Manufacturer") "KNSCHA(科尼盛)"))
      (libsource (lib "easyedapro") (part "189RV0019"))
    )
    (comp (ref "C45")
      (value "1uF")
      (footprint "easyedapro:CAP-SMD_BD6.3-L6.6-W6.6-FD")
      (fields (field (name "Manufacturer Part") "189RV0019") (field (name "Manufacturer") "KNSCHA(科尼盛)"))
      (libsource (lib "easyedapro") (part "189RV0019"))
    )
    (comp (ref "C46")
      (value "1uF")
      (footprint "easyedapro:CAP-SMD_BD6.3-L6.6-W6.6-FD")
      (fields (field (name "Manufacturer Part") "189RV0019") (field (name "Manufacturer") "KNSCHA(科尼盛)"))
      (libsource (lib "easyedapro") (part "189RV0019"))
    )
    (comp (ref "C47")
      (value "100nF")
      (footprint "easyedapro:CAP-TH_L5.0-W2.5-P5.00-D1.0")
      (fields
        (field (name "Manufacturer Part") "CC1H104MC1FD3F6C10MF")
        (field (name "Manufacturer") "Dersonic(德尔创)")
      )
      (libsource (lib "easyedapro") (part "CC1H104MC1FD3F6C10MF"))
    )
    (comp (ref "C48")
      (value "1uF")
      (footprint "easyedapro:CAP-SMD_BD6.3-L6.6-W6.6-FD")
      (fields (field (name "Manufacturer Part") "189RV0019") (field (name "Manufacturer") "KNSCHA(科尼盛)"))
      (libsource (lib "easyedapro") (part "189RV0019"))
    )
    (comp (ref "C49")
      (value "1uF")
      (footprint "easyedapro:CAP-SMD_BD6.3-L6.6-W6.6-FD")
      (fields (field (name "Manufacturer Part") "189RV0019") (field (name "Manufacturer") "KNSCHA(科尼盛)"))
      (libsource (lib "easyedapro") (part "189RV0019"))
    )
    (comp (ref "C50")
      (value "100nF")
      (footprint "easyedapro:CAP-TH_L5.0-W2.5-P5.00-D1.0")
      (fields
        (field (name "Manufacturer Part") "CC1H104MC1FD3F6C10MF")
        (field (name "Manufacturer") "Dersonic(德尔创)")
      )
      (libsource (lib "easyedapro") (part "CC1H104MC1FD3F6C10MF"))
    )
    (comp (ref "C51")
      (value "1uF")
      (footprint "easyedapro:CAP-SMD_BD6.3-L6.6-W6.6-FD")
      (fields (field (name "Manufacturer Part") "189RV0019") (field (name "Manufacturer") "KNSCHA(科尼盛)"))
      (libsource (lib "easyedapro") (part "189RV0019"))
    )
    (comp (ref "C52")
      (value "1uF")
      (footprint "easyedapro:CAP-SMD_BD6.3-L6.6-W6.6-FD")
      (fields (field (name "Manufacturer Part") "189RV0019") (field (name "Manufacturer") "KNSCHA(科尼盛)"))
      (libsource (lib "easyedapro") (part "189RV0019"))
    )
    (comp (ref "D45")
      (value "1N4148PF")
      (footprint "easyedapro:Diode_THT:D_DO-35_SOD27_P7.62mm_Horizontal")
      (fields (field (name "Manufacturer") "ST(先科)"))
      (libsource (lib "easyedapro") (part "Diode_1N4148"))
    )
    (comp (ref "D46")
      (value "1N4148PF")
      (footprint "easyedapro:Diode_THT:D_DO-35_SOD27_P7.62mm_Horizontal")
      (fields (field (name "Manufacturer") "ST(先科)"))
      (libsource (lib "easyedapro") (part "Diode_1N4148"))
    )
    (comp (ref "D47")
      (value "1N4148PF")
      (footprint "easyedapro:Diode_THT:D_DO-35_SOD27_P7.62mm_Horizontal")
      (fields (field (name "Manufacturer") "ST(先科)"))
      (libsource (lib "easyedapro") (part "Diode_1N4148"))
    )
    (comp (ref "D48")
      (value "1N4148PF")
      (footprint "easyedapro:Diode_THT:D_DO-35_SOD27_P7.62mm_Horizontal")
      (fields (field (name "Manufacturer") "ST(先科)"))
      (libsource (lib "easyedapro") (part "Diode_1N4148"))
    )
    (comp (ref "D49")
      (value "1N4148PF")
      (footprint "easyedapro:Diode_THT:D_DO-35_SOD27_P7.62mm_Horizontal")
      (fields (field (name "Manufacturer") "ST(先科)"))
      (libsource (lib "easyedapro") (part "Diode_1N4148"))
    )
    (comp (ref "D50")
      (value "1N4148PF")
      (footprint "easyedapro:Diode_THT:D_DO-35_SOD27_P7.62mm_Horizontal")
      (fields (field (name "Manufacturer") "ST(先科)"))
      (libsource (lib "easyedapro") (part "Diode_1N4148"))
    )
    (comp (ref "J4")
      (value "HC-PJ-320A")
      (footprint "easyedapro:AUDIO-SMD_HC-PJ-320A")
      (fields (field (name "Manufacturer") "HC(虹成电子)"))
      (libsource (lib "easyedapro") (part "HC-PJ-320A"))
    )
    (comp (ref "J5")
      (value "HC-PJ-320A")
      (footprint "easyedapro:AUDIO-SMD_HC-PJ-320A")
      (fields (field (name "Manufacturer") "HC(虹成电子)"))
      (libsource (lib "easyedapro") (part "HC-PJ-320A"))
    )
    (comp (ref "J6")
      (value "HC-PJ-320A")
      (footprint "easyedapro:AUDIO-SMD_HC-PJ-320A")
      (fields (field (name "Manufacturer") "HC(虹成电子)"))
      (libsource (lib "easyedapro") (part "HC-PJ-320A"))
    )
    (comp (ref "J7")
      (value "HC-PJ-320A")
      (footprint "easyedapro:AUDIO-SMD_HC-PJ-320A")
      (fields (field (name "Manufacturer") "HC(虹成电子)"))
      (libsource (lib "easyedapro") (part "HC-PJ-320A"))
    )
    (comp (ref "J8")
      (value "HC-PJ-320A")
      (footprint "easyedapro:AUDIO-SMD_HC-PJ-320A")
      (fields (field (name "Manufacturer") "HC(虹成电子)"))
      (libsource (lib "easyedapro") (part "HC-PJ-320A"))
    )
    (comp (ref "J9")
      (value "HC-PJ-320A")
      (footprint "easyedapro:AUDIO-SMD_HC-PJ-320A")
      (fields (field (name "Manufacturer") "HC(虹成电子)"))
      (libsource (lib "easyedapro") (part "HC-PJ-320A"))
    )
    (comp (ref "R22")
      (value "100kΩ")
      (footprint "easyedapro:Resistor_THT:R_Axial_DIN0204_L3.6mm_D1.6mm_P2.54mm_Vertical")
      (fields
        (field (name "Manufacturer Part") "RN 1/8W 4K7 F T/B A1")
        (field (name "Manufacturer") "Tyohm(幸亚电阻)")
      )
      (libsource (lib "easyedapro") (part "Device_R"))
    )
    (comp (ref "R23")
      (value "10kΩ")
      (footprint "easyedapro:Resistor_THT:R_Axial_DIN0204_L3.6mm_D1.6mm_P2.54mm_Vertical")
      (fields
        (field (name "Manufacturer Part") "RN 1/8W 4K7 F T/B A1")
        (field (name "Manufacturer") "Tyohm(幸亚电阻)")
      )
      (libsource (lib "easyedapro") (part "Device_R"))
    )
    (comp (ref "R24")
      (value "20kΩ")
      (footprint "easyedapro:Resistor_THT:R_Axial_DIN0204_L3.6mm_D1.6mm_P2.54mm_Vertical")
      (fields
        (field (name "Manufacturer Part") "RN 1/8W 4K7 F T/B A1")
        (field (name "Manufacturer") "Tyohm(幸亚电阻)")
      )
      (libsource (lib "easyedapro") (part "Device_R"))
    )
    (comp (ref "R25")
      (value "4.7kΩ")
      (footprint "easyedapro:Resistor_THT:R_Axial_DIN0204_L3.6mm_D1.6mm_P2.54mm_Vertical")
      (fields
        (field (name "Manufacturer Part") "RN 1/8W 4K7 F T/B A1")
        (field (name "Manufacturer") "Tyohm(幸亚电阻)")
      )
      (libsource (lib "easyedapro") (part "Device_R"))
    )
    (comp (ref "R48")
      (value "100kΩ")
      (footprint "easyedapro:Resistor_THT:R_Axial_DIN0204_L3.6mm_D1.6mm_P2.54mm_Vertical")
      (fields
        (field (name "Manufacturer Part") "RN 1/8W 4K7 F T/B A1")
        (field (name "Manufacturer") "Tyohm(幸亚电阻)")
      )
      (libsource (lib "easyedapro") (part "Device_R"))
    )
    (comp (ref "R49")
      (value "10kΩ")
      (footprint "easyedapro:Resistor_THT:R_Axial_DIN0204_L3.6mm_D1.6mm_P2.54mm_Vertical")
      (fields
        (field (name "Manufacturer Part") "RN 1/8W 4K7 F T/B A1")
        (field (name "Manufacturer") "Tyohm(幸亚电阻)")
      )
      (libsource (lib "easyedapro") (part "Device_R"))
    )
    (comp (ref "R50")
      (value "20kΩ")
      (footprint "easyedapro:Resistor_THT:R_Axial_DIN0204_L3.6mm_D1.6mm_P2.54mm_Vertical")
      (fields
        (field (name "Manufacturer Part") "RN 1/8W 4K7 F T/B A1")
        (field (name "Manufacturer") "Tyohm(幸亚电阻)")
      )
      (libsource (lib "easyedapro") (part "Device_R"))
    )
    (comp (ref "R51")
      (value "4.7kΩ")
      (footprint "easyedapro:Resistor_THT:R_Axial_DIN0204_L3.6mm_D1.6mm_P2.54mm_Vertical")
      (fields
        (field (name "Manufacturer Part") "RN 1/8W 4K7 F T/B A1")
        (field (name "Manufacturer") "Tyohm(幸亚电阻)")
      )
      (libsource (lib "easyedapro") (part "Device_R"))
    )
    (comp (ref "R52")
      (value "100kΩ")
      (footprint "easyedapro:Resistor_THT:R_Axial_DIN0204_L3.6mm_D1.6mm_P2.54mm_Vertical")
      (fields
        (field (name "Manufacturer Part") "RN 1/8W 4K7 F T/B A1")
        (field (name "Manufacturer") "Tyohm(幸亚电阻)")
      )
      (libsource (lib "easyedapro") (part "Device_R"))
    )
    (comp (ref "R53")
      (value "10kΩ")
      (footprint "easyedapro:Resistor_THT:R_Axial_DIN0204_L3.6mm_D1.6mm_P2.54mm_Vertical")
      (fields
        (field (name "Manufacturer Part") "RN 1/8W 4K7 F T/B A1")
        (field (name "Manufacturer") "Tyohm(幸亚电阻)")
      )
      (libsource (lib "easyedapro") (part "Device_R"))
    )
    (comp (ref "R54")
      (value "20kΩ")
      (footprint "easyedapro:Resistor_THT:R_Axial_DIN0204_L3.6mm_D1.6mm_P2.54mm_Vertical")
      (fields
        (field (name "Manufacturer Part") "RN 1/8W 4K7 F T/B A1")
        (field (name "Manufacturer") "Tyohm(幸亚电阻)")
      )
      (libsource (lib "easyedapro") (part "Device_R"))
    )
    (comp (ref "R55")
      (value "4.7kΩ")
      (footprint "easyedapro:Resistor_THT:R_Axial_DIN0204_L3.6mm_D1.6mm_P2.54mm_Vertical")
      (fields
        (field (name "Manufacturer Part") "RN 1/8W 4K7 F T/B A1")
        (field (name "Manufacturer") "Tyohm(幸亚电阻)")
      )
      (libsource (lib "easyedapro") (part "Device_R"))
    )
    (comp (ref "R56")
      (value "100kΩ")
      (footprint "easyedapro:Resistor_THT:R_Axial_DIN0204_L3.6mm_D1.6mm_P2.54mm_Vertical")
      (fields
        (field (name "Manufacturer Part") "RN 1/8W 4K7 F T/B A1")
        (field (name "Manufacturer") "Tyohm(幸亚电阻)")
      )
      (libsource (lib "easyedapro") (part "Device_R"))
    )
    (comp (ref "R57")
      (value "10kΩ")
      (footprint "easyedapro:Resistor_THT:R_Axial_DIN0204_L3.6mm_D1.6mm_P2.54mm_Vertical")
      (fields
        (field (name "Manufacturer Part") "RN 1/8W 4K7 F T/B A1")
        (field (name "Manufacturer") "Tyohm(幸亚电阻)")
      )
      (libsource (lib "easyedapro") (part "Device_R"))
    )
    (comp (ref "R58")
      (value "20kΩ")
      (footprint "easyedapro:Resistor_THT:R_Axial_DIN0204_L3.6mm_D1.6mm_P2.54mm_Vertical")
      (fields
        (field (name "Manufacturer Part") "RN 1/8W 4K7 F T/B A1")
        (field (name "Manufacturer") "Tyohm(幸亚电阻)")
      )
      (libsource (lib "easyedapro") (part "Device_R"))
    )
    (comp (ref "R59")
      (value "4.7kΩ")
      (footprint "easyedapro:Resistor_THT:R_Axial_DIN0204_L3.6mm_D1.6mm_P2.54mm_Vertical")
      (fields
        (field (name "Manufacturer Part") "RN 1/8W 4K7 F T/B A1")
        (field (name "Manufacturer") "Tyohm(幸亚电阻)")
      )
      (libsource (lib "easyedapro") (part "Device_R"))
    )
    (comp (ref "R60")
      (value "100kΩ")
      (footprint "easyedapro:Resistor_THT:R_Axial_DIN0204_L3.6mm_D1.6mm_P2.54mm_Vertical")
      (fields
        (field (name "Manufacturer Part") "RN 1/8W 4K7 F T/B A1")
        (field (name "Manufacturer") "Tyohm(幸亚电阻)")
      )
      (libsource (lib "easyedapro") (part "Device_R"))
    )
    (comp (ref "R61")
      (value "10kΩ")
      (footprint "easyedapro:Resistor_THT:R_Axial_DIN0204_L3.6mm_D1.6mm_P2.54mm_Vertical")
      (fields
        (field (name "Manufacturer Part") "RN 1/8W 4K7 F T/B A1")
        (field (name "Manufacturer") "Tyohm(幸亚电阻)")
      )
      (libsource (lib "easyedapro") (part "Device_R"))
    )
    (comp (ref "R62")
      (value "20kΩ")
      (footprint "easyedapro:Resistor_THT:R_Axial_DIN0204_L3.6mm_D1.6mm_P2.54mm_Vertical")
      (fields
        (field (name "Manufacturer Part") "RN 1/8W 4K7 F T/B A1")
        (field (name "Manufacturer") "Tyohm(幸亚电阻)")
      )
      (libsource (lib "easyedapro") (part "Device_R"))
    )
    (comp (ref "R63")
      (value "4.7kΩ")
      (footprint "easyedapro:Resistor_THT:R_Axial_DIN0204_L3.6mm_D1.6mm_P2.54mm_Vertical")
      (fields
        (field (name "Manufacturer Part") "RN 1/8W 4K7 F T/B A1")
        (field (name "Manufacturer") "Tyohm(幸亚电阻)")
      )
      (libsource (lib "easyedapro") (part "Device_R"))
    )
    (comp (ref "R64")
      (value "100kΩ")
      (footprint "easyedapro:Resistor_THT:R_Axial_DIN0204_L3.6mm_D1.6mm_P2.54mm_Vertical")
      (fields
        (field (name "Manufacturer Part") "RN 1/8W 4K7 F T/B A1")
        (field (name "Manufacturer") "Tyohm(幸亚电阻)")
      )
      (libsource (lib "easyedapro") (part "Device_R"))
    )
    (comp (ref "R65")
      (value "10kΩ")
      (footprint "easyedapro:Resistor_THT:R_Axial_DIN0204_L3.6mm_D1.6mm_P2.54mm_Vertical")
      (fields
        (field (name "Manufacturer Part") "RN 1/8W 4K7 F T/B A1")
        (field (name "Manufacturer") "Tyohm(幸亚电阻)")
      )
      (libsource (lib "easyedapro") (part "Device_R"))
    )
    (comp (ref "R66")
      (value "20kΩ")
      (footprint "easyedapro:Resistor_THT:R_Axial_DIN0204_L3.6mm_D1.6mm_P2.54mm_Vertical")
      (fields
        (field (name "Manufacturer Part") "RN 1/8W 4K7 F T/B A1")
        (field (name "Manufacturer") "Tyohm(幸亚电阻)")
      )
      (libsource (lib "easyedapro") (part "Device_R"))
    )
    (comp (ref "R67")
      (value "4.7kΩ")
      (footprint "easyedapro:Resistor_THT:R_Axial_DIN0204_L3.6mm_D1.6mm_P2.54mm_Vertical")
      (fields
        (field (name "Manufacturer Part") "RN 1/8W 4K7 F T/B A1")
        (field (name "Manufacturer") "Tyohm(幸亚电阻)")
      )
      (libsource (lib "easyedapro") (part "Device_R"))
    )
    (comp (ref "U21")
      (value "MCP6002DRG")
      (footprint "easyedapro:SOP-8_L4.9-W3.9-P1.27-LS6.0-BL")
      (fields (field (name "Manufacturer") "HGC(深圳汉芯)"))
      (libsource (lib "easyedapro") (part "MCP6002DRG"))
    )
    (comp (ref "U22")
      (value "MCP6002DRG")
      (footprint "easyedapro:SOP-8_L4.9-W3.9-P1.27-LS6.0-BL")
      (fields (field (name "Manufacturer") "HGC(深圳汉芯)"))
      (libsource (lib "easyedapro") (part "MCP6002DRG"))
    )
    (comp (ref "U23")
      (value "MCP6002DRG")
      (footprint "easyedapro:SOP-8_L4.9-W3.9-P1.27-LS6.0-BL")
      (fields (field (name "Manufacturer") "HGC(深圳汉芯)"))
      (libsource (lib "easyedapro") (part "MCP6002DRG"))
    )
    (comp (ref "C5")
      (value "220uF")
      (footprint "easyedapro:CAP-SMD_BD6.3-L6.6-W6.6-FD")
      (fields (field (name "Manufacturer Part") "189RV0019") (field (name "Manufacturer") "KNSCHA(科尼盛)"))
      (libsource (lib "easyedapro") (part "189RV0019"))
    )
    (comp (ref "C6")
      (value "100nF")
      (footprint "easyedapro:CAP-TH_L5.0-W2.5-P5.00-D1.0")
      (fields
        (field (name "Manufacturer Part") "CC1H104MC1FD3F6C10MF")
        (field (name "Manufacturer") "Dersonic(德尔创)")
      )
      (libsource (lib "easyedapro") (part "CC1H104MC1FD3F6C10MF"))
    )
    (comp (ref "C7")
      (value "100uF")
      (footprint "easyedapro:C1206")
      (description "Capacitance:100uF Tolerance:±20% Tolerance:±20% Voltage Rating:10V Temperature Coefficient:X5R")
      (fields
        (field (name "Manufacturer Part") "HGC1206R5107M100NSPJ")
        (field (name "Manufacturer") "Chinocera(华瓷)")
      )
      (libsource (lib "easyedapro") (part "HGC1206R5107M100NSPJ"))
    )
    (comp (ref "C8")
      (value "1uF")
      (footprint "easyedapro:Capacitor_THT:C_Disc_D3.4mm_W2.1mm_P2.50mm")
      (description "Capacitance:100nF Tolerance:±10% Tolerance:±10% Voltage Rating:63V Temperature Coefficient:-")
      (fields
        (field (name "Manufacturer Part") "CT4G-0805-2X1-63V-0.1μF-K")
        (field (name "Manufacturer") "TORCH(火炬)")
      )
      (libsource (lib "easyedapro") (part "Device_C"))
    )
    (comp (ref "C9")
      (value "100nF")
      (footprint "easyedapro:Capacitor_THT:C_Disc_D3.4mm_W2.1mm_P2.50mm")
      (description "Capacitance:100nF Tolerance:±10% Tolerance:±10% Voltage Rating:63V Temperature Coefficient:-")
      (fields
        (field (name "Manufacturer Part") "CT4G-0805-2X1-63V-0.1μF-K")
        (field (name "Manufacturer") "TORCH(火炬)")
      )
      (libsource (lib "easyedapro") (part "Device_C"))
    )
    (comp (ref "D44")
      (value "SA6.0A")
      (footprint "easyedapro:DO-15_BD3.1-L6.7-P10.70-D0.8-RD")
      (fields (field (name "Manufacturer") "Littelfuse(美国力特)"))
      (libsource (lib "easyedapro") (part "SA6.0A_C1973281"))
    )
    (comp (ref "F1")
      (value "nSMD050-33V")
      (footprint "easyedapro:F1206")
      (description "Voltage - Max:33V Current - Max:100A Hold Current:500mA Trip Current:1A")
      (fields (field (name "Manufacturer") "台湾陆海"))
      (libsource (lib "easyedapro") (part "nSMD050-33V"))
    )
    (comp (ref "J1")
      (value "DC005")
      (footprint "easyedapro:DC-IN-TH_DC005")
      (fields (field (name "Manufacturer") "SHOU HAN(首韩)"))
      (libsource (lib "easyedapro") (part "DC005_C431533"))
    )
    (comp (ref "R20")
      (value "33Ω")
      (footprint "easyedapro:Resistor_THT:R_Axial_DIN0204_L3.6mm_D1.6mm_P2.54mm_Vertical")
      (fields
        (field (name "Manufacturer Part") "RN1/8W10KFT/BA1")
        (field (name "Manufacturer") "Tyohm(幸亚电阻)")
      )
      (libsource (lib "easyedapro") (part "Device_R"))
    )
    (comp (ref "SW1")
      (value "HX B3F-4055-Y")
      (footprint "easyedapro:Button_Switch_SMD:SW_SPST_PTS645")
      (fields (field (name "Manufacturer") "hanxia(韩下)"))
      (libsource (lib "easyedapro") (part "Switch_SW_Push"))
    )
    (comp (ref "SW2")
      (value "HX B3F-4055-Y")
      (footprint "easyedapro:Button_Switch_SMD:SW_SPST_PTS645")
      (fields (field (name "Manufacturer") "hanxia(韩下)"))
      (libsource (lib "easyedapro") (part "Switch_SW_Push"))
    )
    (comp (ref "SW3")
      (value "HX B3F-4055-Y")
      (footprint "easyedapro:Button_Switch_SMD:SW_SPST_PTS645")
      (fields (field (name "Manufacturer") "hanxia(韩下)"))
      (libsource (lib "easyedapro") (part "Switch_SW_Push"))
    )
    (comp (ref "SW4")
      (value "HX B3F-4055-Y")
      (footprint "easyedapro:Button_Switch_SMD:SW_SPST_PTS645")
      (fields (field (name "Manufacturer") "hanxia(韩下)"))
      (libsource (lib "easyedapro") (part "Switch_SW_Push"))
    )
    (comp (ref "SW5")
      (value "HX B3F-4055-Y")
      (footprint "easyedapro:Button_Switch_SMD:SW_SPST_PTS645")
      (fields (field (name "Manufacturer") "hanxia(韩下)"))
      (libsource (lib "easyedapro") (part "Switch_SW_Push"))
    )
    (comp (ref "SW6")
      (value "HX B3F-4055-Y")
      (footprint "easyedapro:Button_Switch_SMD:SW_SPST_PTS645")
      (fields (field (name "Manufacturer") "hanxia(韩下)"))
      (libsource (lib "easyedapro") (part "Switch_SW_Push"))
    )
    (comp (ref "SW7")
      (value "HX B3F-4055-Y")
      (footprint "easyedapro:Button_Switch_SMD:SW_SPST_PTS645")
      (fields (field (name "Manufacturer") "hanxia(韩下)"))
      (libsource (lib "easyedapro") (part "Switch_SW_Push"))
    )
    (comp (ref "SW8")
      (value "HX B3F-4055-Y")
      (footprint "easyedapro:Button_Switch_SMD:SW_SPST_PTS645")
      (fields (field (name "Manufacturer") "hanxia(韩下)"))
      (libsource (lib "easyedapro") (part "Switch_SW_Push"))
    )
    (comp (ref "SW9")
      (value "HX B3F-4055-Y")
      (footprint "easyedapro:Button_Switch_SMD:SW_SPST_PTS645")
      (fields (field (name "Manufacturer") "hanxia(韩下)"))
      (libsource (lib "easyedapro") (part "Switch_SW_Push"))
    )
    (comp (ref "SW10")
      (value "HX B3F-4055-Y")
      (footprint "easyedapro:Button_Switch_SMD:SW_SPST_PTS645")
      (fields (field (name "Manufacturer") "hanxia(韩下)"))
      (libsource (lib "easyedapro") (part "Switch_SW_Push"))
    )
    (comp (ref "SW11")
      (value "HX B3F-4055-Y")
      (footprint "easyedapro:Button_Switch_SMD:SW_SPST_PTS645")
      (fields (field (name "Manufacturer") "hanxia(韩下)"))
      (libsource (lib "easyedapro") (part "Switch_SW_Push"))
    )
    (comp (ref "SW12")
      (value "HX B3F-4055-Y")
      (footprint "easyedapro:Button_Switch_SMD:SW_SPST_PTS645")
      (fields (field (name "Manufacturer") "hanxia(韩下)"))
      (libsource (lib "easyedapro") (part "Switch_SW_Push"))
    )
    (comp (ref "SW13")
      (value "HX B3F-4055-Y")
      (footprint "easyedapro:Button_Switch_SMD:SW_SPST_PTS645")
      (fields (field (name "Manufacturer") "hanxia(韩下)"))
      (libsource (lib "easyedapro") (part "Switch_SW_Push"))
    )
    (comp (ref "SW14")
      (value "HX B3F-4055-Y")
      (footprint "easyedapro:Button_Switch_SMD:SW_SPST_PTS645")
      (fields (field (name "Manufacturer") "hanxia(韩下)"))
      (libsource (lib "easyedapro") (part "Switch_SW_Push"))
    )
    (comp (ref "SW15")
      (value "HX B3F-4055-Y")
      (footprint "easyedapro:Button_Switch_SMD:SW_SPST_PTS645")
      (fields (field (name "Manufacturer") "hanxia(韩下)"))
      (libsource (lib "easyedapro") (part "Switch_SW_Push"))
    )
    (comp (ref "SW16")
      (value "HX B3F-4055-Y")
      (footprint "easyedapro:Button_Switch_SMD:SW_SPST_PTS645")
      (fields (field (name "Manufacturer") "hanxia(韩下)"))
      (libsource (lib "easyedapro") (part "Switch_SW_Push"))
    )
    (comp (ref "SW17")
      (value "HX B3F-4055-Y")
      (footprint "easyedapro:Button_Switch_SMD:SW_SPST_PTS645")
      (fields (field (name "Manufacturer") "hanxia(韩下)"))
      (libsource (lib "easyedapro") (part "Switch_SW_Push"))
    )
    (comp (ref "SW18")
      (value "HX B3F-4055-Y")
      (footprint "easyedapro:Button_Switch_SMD:SW_SPST_PTS645")
      (fields (field (name "Manufacturer") "hanxia(韩下)"))
      (libsource (lib "easyedapro") (part "Switch_SW_Push"))
    )
    (comp (ref "SW19")
      (value "HX B3F-4055-Y")
      (footprint "easyedapro:Button_Switch_SMD:SW_SPST_PTS645")
      (fields (field (name "Manufacturer") "hanxia(韩下)"))
      (libsource (lib "easyedapro") (part "Switch_SW_Push"))
    )
    (comp (ref "SW20")
      (value "HX B3F-4055-Y")
      (footprint "easyedapro:Button_Switch_SMD:SW_SPST_PTS645")
      (fields (field (name "Manufacturer") "hanxia(韩下)"))
      (libsource (lib "easyedapro") (part "Switch_SW_Push"))
    )
    (comp (ref "SW21")
      (value "HX B3F-4055-Y")
      (footprint "easyedapro:Button_Switch_SMD:SW_SPST_PTS645")
      (fields (field (name "Manufacturer") "hanxia(韩下)"))
      (libsource (lib "easyedapro") (part "Switch_SW_Push"))
    )
    (comp (ref "SW22")
      (value "HX B3F-4055-Y")
      (footprint "easyedapro:Button_Switch_SMD:SW_SPST_PTS645")
      (fields (field (name "Manufacturer") "hanxia(韩下)"))
      (libsource (lib "easyedapro") (part "Switch_SW_Push"))
    )
    (comp (ref "SW23")
      (value "HX B3F-4055-Y")
      (footprint "easyedapro:Button_Switch_SMD:SW_SPST_PTS645")
      (fields (field (name "Manufacturer") "hanxia(韩下)"))
      (libsource (lib "easyedapro") (part "Switch_SW_Push"))
    )
    (comp (ref "SW24")
      (value "HX B3F-4055-Y")
      (footprint "easyedapro:Button_Switch_SMD:SW_SPST_PTS645")
      (fields (field (name "Manufacturer") "hanxia(韩下)"))
      (libsource (lib "easyedapro") (part "Switch_SW_Push"))
    )
    (comp (ref "SW25")
      (value "HX B3F-4055-Y")
      (footprint "easyedapro:Button_Switch_SMD:SW_SPST_PTS645")
      (fields (field (name "Manufacturer") "hanxia(韩下)"))
      (libsource (lib "easyedapro") (part "Switch_SW_Push"))
    )
    (comp (ref "SW26")
      (value "HX B3F-4055-Y")
      (footprint "easyedapro:Button_Switch_SMD:SW_SPST_PTS645")
      (fields (field (name "Manufacturer") "hanxia(韩下)"))
      (libsource (lib "easyedapro") (part "Switch_SW_Push"))
    )
    (comp (ref "SW27")
      (value "HX B3F-4055-Y")
      (footprint "easyedapro:Button_Switch_SMD:SW_SPST_PTS645")
      (fields (field (name "Manufacturer") "hanxia(韩下)"))
      (libsource (lib "easyedapro") (part "Switch_SW_Push"))
    )
    (comp (ref "SW28")
      (value "HX B3F-4055-Y")
      (footprint "easyedapro:Button_Switch_SMD:SW_SPST_PTS645")
      (fields (field (name "Manufacturer") "hanxia(韩下)"))
      (libsource (lib "easyedapro") (part "Switch_SW_Push"))
    )
    (comp (ref "SW29")
      (value "HX B3F-4055-Y")
      (footprint "easyedapro:Button_Switch_SMD:SW_SPST_PTS645")
      (fields (field (name "Manufacturer") "hanxia(韩下)"))
      (libsource (lib "easyedapro") (part "Switch_SW_Push"))
    )
    (comp (ref "SW30")
      (value "HX B3F-4055-Y")
      (footprint "easyedapro:Button_Switch_SMD:SW_SPST_PTS645")
      (fields (field (name "Manufacturer") "hanxia(韩下)"))
      (libsource (lib "easyedapro") (part "Switch_SW_Push"))
    )
    (comp (ref "SW31")
      (value "HX B3F-4055-Y")
      (footprint "easyedapro:Button_Switch_SMD:SW_SPST_PTS645")
      (fields (field (name "Manufacturer") "hanxia(韩下)"))
      (libsource (lib "easyedapro") (part "Switch_SW_Push"))
    )
    (comp (ref "SW32")
      (value "HX B3F-4055-Y")
      (footprint "easyedapro:Button_Switch_SMD:SW_SPST_PTS645")
      (fields (field (name "Manufacturer") "hanxia(韩下)"))
      (libsource (lib "easyedapro") (part "Switch_SW_Push"))
    )
    (comp (ref "SW33")
      (value "HX B3F-4055-Y")
      (footprint "easyedapro:Button_Switch_SMD:SW_SPST_PTS645")
      (fields (field (name "Manufacturer") "hanxia(韩下)"))
      (libsource (lib "easyedapro") (part "Switch_SW_Push"))
    )
    (comp (ref "SW34")
      (value "HX B3F-4055-Y")
      (footprint "easyedapro:Button_Switch_SMD:SW_SPST_PTS645")
      (fields (field (name "Manufacturer") "hanxia(韩下)"))
      (libsource (lib "easyedapro") (part "Switch_SW_Push"))
    )
    (comp (ref "SW35")
      (value "HX B3F-4055-Y")
      (footprint "easyedapro:Button_Switch_SMD:SW_SPST_PTS645")
      (fields (field (name "Manufacturer") "hanxia(韩下)"))
      (libsource (lib "easyedapro") (part "Switch_SW_Push"))
    )
    (comp (ref "SW36")
      (value "HX B3F-4055-Y")
      (footprint "easyedapro:Button_Switch_SMD:SW_SPST_PTS645")
      (fields (field (name "Manufacturer") "hanxia(韩下)"))
      (libsource (lib "easyedapro") (part "Switch_SW_Push"))
    )
    (comp (ref "SW37")
      (value "HX B3F-4055-Y")
      (footprint "easyedapro:Button_Switch_SMD:SW_SPST_PTS645")
      (fields (field (name "Manufacturer") "hanxia(韩下)"))
      (libsource (lib "easyedapro") (part "Switch_SW_Push"))
    )
    (comp (ref "SW38")
      (value "HX B3F-4055-Y")
      (footprint "easyedapro:Button_Switch_SMD:SW_SPST_PTS645")
      (fields (field (name "Manufacturer") "hanxia(韩下)"))
      (libsource (lib "easyedapro") (part "Switch_SW_Push"))
    )
    (comp (ref "SW39")
      (value "HX B3F-4055-Y")
      (footprint "easyedapro:Button_Switch_SMD:SW_SPST_PTS645")
      (fields (field (name "Manufacturer") "hanxia(韩下)"))
      (libsource (lib "easyedapro") (part "Switch_SW_Push"))
    )
    (comp (ref "SW40")
      (value "HX B3F-4055-Y")
      (footprint "easyedapro:Button_Switch_SMD:SW_SPST_PTS645")
      (fields (field (name "Manufacturer") "hanxia(韩下)"))
      (libsource (lib "easyedapro") (part "Switch_SW_Push"))
    )
    (comp (ref "SW41")
      (value "HX B3F-4055-Y")
      (footprint "easyedapro:Button_Switch_SMD:SW_SPST_PTS645")
      (fields (field (name "Manufacturer") "hanxia(韩下)"))
      (libsource (lib "easyedapro") (part "Switch_SW_Push"))
    )
    (comp (ref "SW42")
      (value "HX B3F-4055-Y")
      (footprint "easyedapro:Button_Switch_SMD:SW_SPST_PTS645")
      (fields (field (name "Manufacturer") "hanxia(韩下)"))
      (libsource (lib "easyedapro") (part "Switch_SW_Push"))
    )
    (comp (ref "SW49")
      (value "TK-6580A-1")
      (footprint "easyedapro:SW-TH_TK-6580A-1")
      (fields (field (name "Manufacturer") "Yuandi(元迪)"))
      (libsource (lib "easyedapro") (part "TK-6580A-1"))
    )
    (comp (ref "U6")
      (value "1812L200/33GR")
      (footprint "easyedapro:F1812")
      (fields (field (name "Manufacturer") "LUTE(陆特)"))
      (libsource (lib "easyedapro") (part "1812L200/33GR"))
    )
    (comp (ref "U8")
      (value "SN74AHCT125N")
      (footprint "easyedapro:PDIP-14_L19.3-W6.4-P2.54-LS7.6-BL")
      (fields (field (name "Manufacturer") "TI(德州仪器)"))
      (libsource (lib "easyedapro") (part "SN74AHCT125N"))
    )
  )
  (nets
    (net (code "1") (name "3VDC") (class "Default")
      (node (ref "C25") (pin "2") (pinfunction "2_2") (pintype "unspecified"))
      (node (ref "C3") (pin "2") (pinfunction "~_2") (pintype "unspecified"))
      (node (ref "C4") (pin "2") (pinfunction "~_2") (pintype "unspecified"))
      (node (ref "C54") (pin "1") (pinfunction "~_1") (pintype "unspecified"))
      (node (ref "C56") (pin "1") (pinfunction "1_1") (pintype "input"))
      (node (ref "COL_MUX1") (pin "24") (pinfunction "VCC_24") (pintype "unspecified"))
      (node (ref "R2") (pin "1") (pinfunction "~_1") (pintype "unspecified"))
      (node (ref "R69") (pin "1") (pinfunction "~_1") (pintype "unspecified"))
      (node (ref "ROW_MUX1") (pin "24") (pinfunction "VCC_24") (pintype "unspecified"))
      (node (ref "RV1") (pin "1") (pinfunction "1_1") (pintype "unspecified"))
      (node (ref "RV2") (pin "1") (pinfunction "1_1") (pintype "unspecified"))
      (node (ref "RV3") (pin "1") (pinfunction "1_1") (pintype "unspecified"))
      (node (ref "SW43") (pin "2") (pinfunction "2_2") (pintype "unspecified"))
      (node (ref "SW44") (pin "2") (pinfunction "2_2") (pintype "unspecified"))
      (node (ref "SW45") (pin "2") (pinfunction "2_2") (pintype "unspecified"))
      (node (ref "SW46") (pin "2") (pinfunction "2_2") (pintype "unspecified"))
      (node (ref "SW47") (pin "2") (pinfunction "2_2") (pintype "unspecified"))
      (node (ref "SW48") (pin "2") (pinfunction "2_2") (pintype "unspecified"))
      (node (ref "Screen1") (pin "2") (pinfunction "Pin_2_2") (pintype "unspecified"))
      (node (ref "U1") (pin "3.3V_2") (pinfunction "3.3V_2_3.3V_2") (pintype "unspecified"))
      (node (ref "U21") (pin "8") (pinfunction "VDD_8") (pintype "unspecified"))
    )
    (net (code "2") (name "5VDC") (class "Default")
      (node (ref "C10") (pin "2") (pinfunction "~_2") (pintype "unspecified"))
      (node (ref "C8") (pin "1") (pinfunction "~_1") (pintype "unspecified"))
      (node (ref "C9") (pin "1") (pinfunction "~_1") (pintype "unspecified"))
      (node (ref "R4") (pin "2") (pinfunction "~_2") (pintype "unspecified"))
      (node (ref "R70") (pin "2") (pinfunction "~_2") (pintype "unspecified"))
      (node (ref "SW49") (pin "5") (pinfunction "5_5") (pintype "unspecified"))
      (node (ref "U5") (pin "7") (pinfunction "VO1_7") (pintype "unspecified"))
      (node (ref "U8") (pin "14") (pinfunction "VCC_14") (pintype "unspecified"))
    )
    (net (code "3") (name "CNTRLLP") (class "Default")
      (node (ref "C57") (pin "1") (pinfunction "~_1") (pintype "unspecified"))
      (node (ref "D42") (pin "3") (pinfunction "VSS_3") (pintype "unspecified"))
      (node (ref "D51") (pin "1") (pinfunction "VDD_1") (pintype "unspecified"))
    )
    (net (code "4") (name "CNTRL_LED") (class "Default")
      (node (ref "D42") (pin "2") (pinfunction "DOUT_2") (pintype "output"))
      (node (ref "D51") (pin "4") (pinfunction "DIN_4") (pintype "input"))
    )
    (net (code "5") (name "COL1") (class "Default")
      (node (ref "COL_MUX1") (pin "9") (pinfunction "I0_9") (pintype "unspecified"))
      (node (ref "SW1") (pin "2") (pinfunction "2_2") (pintype "unspecified"))
      (node (ref "SW2") (pin "2") (pinfunction "2_2") (pintype "unspecified"))
      (node (ref "SW3") (pin "2") (pinfunction "2_2") (pintype "unspecified"))
      (node (ref "SW4") (pin "2") (pinfunction "2_2") (pintype "unspecified"))
      (node (ref "SW5") (pin "2") (pinfunction "2_2") (pintype "unspecified"))
      (node (ref "SW6") (pin "2") (pinfunction "2_2") (pintype "unspecified"))
      (node (ref "SW7") (pin "2") (pinfunction "2_2") (pintype "unspecified"))
    )
    (net (code "6") (name "COL2") (class "Default")
      (node (ref "COL_MUX1") (pin "8") (pinfunction "I1_8") (pintype "unspecified"))
      (node (ref "SW10") (pin "2") (pinfunction "2_2") (pintype "unspecified"))
      (node (ref "SW11") (pin "2") (pinfunction "2_2") (pintype "unspecified"))
      (node (ref "SW12") (pin "2") (pinfunction "2_2") (pintype "unspecified"))
      (node (ref "SW13") (pin "2") (pinfunction "2_2") (pintype "unspecified"))
      (node (ref "SW14") (pin "2") (pinfunction "2_2") (pintype "unspecified"))
      (node (ref "SW8") (pin "2") (pinfunction "2_2") (pintype "unspecified"))
      (node (ref "SW9") (pin "2") (pinfunction "2_2") (pintype "unspecified"))
    )
    (net (code "7") (name "COL3") (class "Default")
      (node (ref "COL_MUX1") (pin "7") (pinfunction "I2_7") (pintype "unspecified"))
      (node (ref "SW15") (pin "2") (pinfunction "2_2") (pintype "unspecified"))
      (node (ref "SW16") (pin "2") (pinfunction "2_2") (pintype "unspecified"))
      (node (ref "SW17") (pin "2") (pinfunction "2_2") (pintype "unspecified"))
      (node (ref "SW18") (pin "2") (pinfunction "2_2") (pintype "unspecified"))
      (node (ref "SW19") (pin "2") (pinfunction "2_2") (pintype "unspecified"))
      (node (ref "SW20") (pin "2") (pinfunction "2_2") (pintype "unspecified"))
      (node (ref "SW21") (pin "2") (pinfunction "2_2") (pintype "unspecified"))
    )
    (net (code "8") (name "COL4") (class "Default")
      (node (ref "COL_MUX1") (pin "6") (pinfunction "I3_6") (pintype "unspecified"))
      (node (ref "SW22") (pin "2") (pinfunction "2_2") (pintype "unspecified"))
      (node (ref "SW23") (pin "2") (pinfunction "2_2") (pintype "unspecified"))
      (node (ref "SW24") (pin "2") (pinfunction "2_2") (pintype "unspecified"))
      (node (ref "SW25") (pin "2") (pinfunction "2_2") (pintype "unspecified"))
      (node (ref "SW26") (pin "2") (pinfunction "2_2") (pintype "unspecified"))
      (node (ref "SW27") (pin "2") (pinfunction "2_2") (pintype "unspecified"))
      (node (ref "SW28") (pin "2") (pinfunction "2_2") (pintype "unspecified"))
    )
    (net (code "9") (name "COL5") (class "Default")
      (node (ref "COL_MUX1") (pin "5") (pinfunction "I4_5") (pintype "unspecified"))
      (node (ref "SW29") (pin "2") (pinfunction "2_2") (pintype "unspecified"))
      (node (ref "SW30") (pin "2") (pinfunction "2_2") (pintype "unspecified"))
      (node (ref "SW31") (pin "2") (pinfunction "2_2") (pintype "unspecified"))
      (node (ref "SW32") (pin "2") (pinfunction "2_2") (pintype "unspecified"))
      (node (ref "SW33") (pin "2") (pinfunction "2_2") (pintype "unspecified"))
      (node (ref "SW34") (pin "2") (pinfunction "2_2") (pintype "unspecified"))
      (node (ref "SW35") (pin "2") (pinfunction "2_2") (pintype "unspecified"))
    )
    (net (code "10") (name "COL6") (class "Default")
      (node (ref "COL_MUX1") (pin "4") (pinfunction "I5_4") (pintype "unspecified"))
      (node (ref "SW36") (pin "2") (pinfunction "2_2") (pintype "unspecified"))
      (node (ref "SW37") (pin "2") (pinfunction "2_2") (pintype "unspecified"))
      (node (ref "SW38") (pin "2") (pinfunction "2_2") (pintype "unspecified"))
      (node (ref "SW39") (pin "2") (pinfunction "2_2") (pintype "unspecified"))
      (node (ref "SW40") (pin "2") (pinfunction "2_2") (pintype "unspecified"))
      (node (ref "SW41") (pin "2") (pinfunction "2_2") (pintype "unspecified"))
      (node (ref "SW42") (pin "2") (pinfunction "2_2") (pintype "unspecified"))
    )
    (net (code "11") (name "CTRL1") (class "Default")
      (node (ref "COL_MUX1") (pin "2") (pinfunction "I7_2") (pintype "unspecified"))
      (node (ref "SW43") (pin "1") (pinfunction "1_1") (pintype "unspecified"))
    )
    (net (code "12") (name "CTRL2") (class "Default")
      (node (ref "COL_MUX1") (pin "23") (pinfunction "I8_23") (pintype "unspecified"))
      (node (ref "SW44") (pin "1") (pinfunction "1_1") (pintype "unspecified"))
    )
    (net (code "13") (name "CTRL3") (class "Default")
      (node (ref "COL_MUX1") (pin "22") (pinfunction "I9_22") (pintype "unspecified"))
      (node (ref "SW45") (pin "1") (pinfunction "1_1") (pintype "unspecified"))
    )
    (net (code "14") (name "CTRL4") (class "Default")
      (node (ref "COL_MUX1") (pin "21") (pinfunction "I10_21") (pintype "unspecified"))
      (node (ref "SW46") (pin "1") (pinfunction "1_1") (pintype "unspecified"))
    )
    (net (code "15") (name "CTRL5") (class "Default")
      (node (ref "COL_MUX1") (pin "20") (pinfunction "I11_20") (pintype "unspecified"))
      (node (ref "SW47") (pin "1") (pinfunction "1_1") (pintype "unspecified"))
    )
    (net (code "16") (name "CTRL6") (class "Default")
      (node (ref "COL_MUX1") (pin "19") (pinfunction "I12_19") (pintype "unspecified"))
      (node (ref "SW48") (pin "1") (pinfunction "1_1") (pintype "unspecified"))
    )
    (net (code "17") (name "E1") (class "Default")
      (node (ref "C12") (pin "1") (pinfunction "1_1") (pintype "input"))
      (node (ref "R25") (pin "2") (pinfunction "~_2") (pintype "unspecified"))
      (node (ref "U1") (pin "14") (pinfunction "14_14") (pintype "bidirectional"))
    )
    (net (code "18") (name "E2") (class "Default")
      (node (ref "C43") (pin "1") (pinfunction "1_1") (pintype "input"))
      (node (ref "R55") (pin "2") (pinfunction "~_2") (pintype "unspecified"))
      (node (ref "U1") (pin "15") (pinfunction "15_15") (pintype "bidirectional"))
    )
    (net (code "19") (name "E3") (class "Default")
      (node (ref "C46") (pin "1") (pinfunction "1_1") (pintype "input"))
      (node (ref "R59") (pin "2") (pinfunction "~_2") (pintype "unspecified"))
      (node (ref "U1") (pin "16") (pinfunction "16_16") (pintype "bidirectional"))
    )
    (net (code "20") (name "E4") (class "Default")
      (node (ref "C40") (pin "1") (pinfunction "1_1") (pintype "input"))
      (node (ref "R51") (pin "2") (pinfunction "~_2") (pintype "unspecified"))
      (node (ref "U1") (pin "17") (pinfunction "17_17") (pintype "bidirectional"))
    )
    (net (code "21") (name "E5") (class "Default")
      (node (ref "C49") (pin "1") (pinfunction "1_1") (pintype "input"))
      (node (ref "R63") (pin "2") (pinfunction "~_2") (pintype "unspecified"))
      (node (ref "U1") (pin "20") (pinfunction "20_20") (pintype "bidirectional"))
    )
    (net (code "22") (name "E6") (class "Default")
      (node (ref "C52") (pin "1") (pinfunction "1_1") (pintype "input"))
      (node (ref "R67") (pin "2") (pinfunction "~_2") (pintype "unspecified"))
      (node (ref "U1") (pin "21") (pinfunction "21_21") (pintype "bidirectional"))
    )
    (net (code "23") (name "FP1") (class "Default")
      (node (ref "COL_MUX1") (pin "17") (pinfunction "I14_17") (pintype "unspecified"))
      (node (ref "RV1") (pin "2") (pinfunction "2_2") (pintype "unspecified"))
    )
    (net (code "24") (name "FP2") (class "Default")
      (node (ref "COL_MUX1") (pin "16") (pinfunction "I15_16") (pintype "unspecified"))
      (node (ref "RV2") (pin "2") (pinfunction "2_2") (pintype "unspecified"))
    )
    (net (code "25") (name "GND") (class "Default")
      (node (ref "C10") (pin "1") (pinfunction "~_1") (pintype "unspecified"))
      (node (ref "C12") (pin "2") (pinfunction "2_2") (pintype "input"))
      (node (ref "C2") (pin "2") (pinfunction "~_2") (pintype "unspecified"))
      (node (ref "C3") (pin "1") (pinfunction "~_1") (pintype "unspecified"))
      (node (ref "C31") (pin "2") (pinfunction "~_2") (pintype "unspecified"))
      (node (ref "C32") (pin "2") (pinfunction "~_2") (pintype "unspecified"))
      (node (ref "C33") (pin "2") (pinfunction "~_2") (pintype "unspecified"))
      (node (ref "C34") (pin "2") (pinfunction "~_2") (pintype "unspecified"))
      (node (ref "C35") (pin "2") (pinfunction "~_2") (pintype "unspecified"))
      (node (ref "C36") (pin "2") (pinfunction "~_2") (pintype "unspecified"))
      (node (ref "C4") (pin "1") (pinfunction "~_1") (pintype "unspecified"))
      (node (ref "C40") (pin "2") (pinfunction "2_2") (pintype "input"))
      (node (ref "C43") (pin "2") (pinfunction "2_2") (pintype "input"))
      (node (ref "C46") (pin "2") (pinfunction "2_2") (pintype "input"))
      (node (ref "C49") (pin "2") (pinfunction "2_2") (pintype "input"))
      (node (ref "C5") (pin "1") (pinfunction "1_1") (pintype "input"))
      (node (ref "C52") (pin "2") (pinfunction "2_2") (pintype "input"))
      (node (ref "C54") (pin "2") (pinfunction "~_2") (pintype "unspecified"))
      (node (ref "C56") (pin "2") (pinfunction "2_2") (pintype "input"))
      (node (ref "C57") (pin "2") (pinfunction "~_2") (pintype "unspecified"))
      (node (ref "C59") (pin "2") (pinfunction "~_2") (pintype "unspecified"))
      (node (ref "C6") (pin "1") (pinfunction "1_1") (pintype "unspecified"))
      (node (ref "C7") (pin "1") (pinfunction "1_1") (pintype "unspecified"))
      (node (ref "C8") (pin "2") (pinfunction "~_2") (pintype "unspecified"))
      (node (ref "C9") (pin "2") (pinfunction "~_2") (pintype "unspecified"))
      (node (ref "COL_MUX1") (pin "12") (pinfunction "GND_12") (pintype "unspecified"))
      (node (ref "COL_MUX1") (pin "15") (pinfunction "~{E}_15") (pintype "input"))
      (node (ref "COL_MUX1") (pin "3") (pinfunction "I6_3") (pintype "unspecified"))
      (node (ref "D44") (pin "2") (pinfunction "A_2") (pintype "input"))
      (node (ref "D56") (pin "3") (pinfunction "VSS_3") (pintype "unspecified"))
      (node (ref "D58") (pin "2") (pinfunction "DOUT_2") (pintype "output"))
      (node (ref "D58") (pin "3") (pinfunction "VSS_3") (pintype "unspecified"))
      (node (ref "J1") (pin "2") (pinfunction "2_2") (pintype "unspecified"))
      (node (ref "J1") (pin "3") (pinfunction "3_3") (pintype "unspecified"))
      (node (ref "J10") (pin "1") (pinfunction "1_1") (pintype "unspecified"))
      (node (ref "J10") (pin "3") (pinfunction "3_3") (pintype "unspecified"))
      (node (ref "J11") (pin "1") (pinfunction "1_1") (pintype "unspecified"))
      (node (ref "J11") (pin "3") (pinfunction "3_3") (pintype "unspecified"))
      (node (ref "J2") (pin "2") (pinfunction "2_2") (pintype "unspecified"))
      (node (ref "J3") (pin "2") (pinfunction "2_2") (pintype "unspecified"))
      (node (ref "J4") (pin "1") (pinfunction "1_1") (pintype "unspecified"))
      (node (ref "J4") (pin "2") (pinfunction "2_2") (pintype "unspecified"))
      (node (ref "J4") (pin "3") (pinfunction "3_3") (pintype "unspecified"))
      (node (ref "J5") (pin "1") (pinfunction "1_1") (pintype "unspecified"))
      (node (ref "J5") (pin "2") (pinfunction "2_2") (pintype "unspecified"))
      (node (ref "J5") (pin "3") (pinfunction "3_3") (pintype "unspecified"))
      (node (ref "J6") (pin "1") (pinfunction "1_1") (pintype "unspecified"))
      (node (ref "J6") (pin "2") (pinfunction "2_2") (pintype "unspecified"))
      (node (ref "J6") (pin "3") (pinfunction "3_3") (pintype "unspecified"))
      (node (ref "J7") (pin "1") (pinfunction "1_1") (pintype "unspecified"))
      (node (ref "J7") (pin "2") (pinfunction "2_2") (pintype "unspecified"))
      (node (ref "J7") (pin "3") (pinfunction "3_3") (pintype "unspecified"))
      (node (ref "J8") (pin "1") (pinfunction "1_1") (pintype "unspecified"))
      (node (ref "J8") (pin "2") (pinfunction "2_2") (pintype "unspecified"))
      (node (ref "J8") (pin "3") (pinfunction "3_3") (pintype "unspecified"))
      (node (ref "J9") (pin "1") (pinfunction "1_1") (pintype "unspecified"))
      (node (ref "J9") (pin "2") (pinfunction "2_2") (pintype "unspecified"))
      (node (ref "J9") (pin "3") (pinfunction "3_3") (pintype "unspecified"))
      (node (ref "LEDPWR1") (pin "1") (pinfunction "C_1") (pintype "input"))
      (node (ref "R22") (pin "1") (pinfunction "~_1") (pintype "unspecified"))
      (node (ref "R24") (pin "2") (pinfunction "~_2") (pintype "unspecified"))
      (node (ref "R48") (pin "1") (pinfunction "~_1") (pintype "unspecified"))
      (node (ref "R50") (pin "2") (pinfunction "~_2") (pintype "unspecified"))
      (node (ref "R52") (pin "1") (pinfunction "~_1") (pintype "unspecified"))
      (node (ref "R54") (pin "2") (pinfunction "~_2") (pintype "unspecified"))
      (node (ref "R56") (pin "1") (pinfunction "~_1") (pintype "unspecified"))
      (node (ref "R58") (pin "2") (pinfunction "~_2") (pintype "unspecified"))
      (node (ref "R60") (pin "1") (pinfunction "~_1") (pintype "unspecified"))
      (node (ref "R62") (pin "2") (pinfunction "~_2") (pintype "unspecified"))
      (node (ref "R64") (pin "1") (pinfunction "~_1") (pintype "unspecified"))
      (node (ref "R66") (pin "2") (pinfunction "~_2") (pintype "unspecified"))
      (node (ref "ROW_MUX1") (pin "12") (pinfunction "GND_12") (pintype "unspecified"))
      (node (ref "ROW_MUX1") (pin "15") (pinfunction "~{E}_15") (pintype "input"))
      (node (ref "ROW_MUX1") (pin "16") (pinfunction "I15_16") (pintype "unspecified"))
      (node (ref "ROW_MUX1") (pin "17") (pinfunction "I14_17") (pintype "unspecified"))
      (node (ref "ROW_MUX1") (pin "18") (pinfunction "I13_18") (pintype "unspecified"))
      (node (ref "ROW_MUX1") (pin "19") (pinfunction "I12_19") (pintype "unspecified"))
      (node (ref "ROW_MUX1") (pin "20") (pinfunction "I11_20") (pintype "unspecified"))
      (node (ref "ROW_MUX1") (pin "21") (pinfunction "I10_21") (pintype "unspecified"))
      (node (ref "ROW_MUX1") (pin "22") (pinfunction "I9_22") (pintype "unspecified"))
      (node (ref "ROW_MUX1") (pin "23") (pinfunction "I8_23") (pintype "unspecified"))
      (node (ref "RV1") (pin "3") (pinfunction "3_3") (pintype "unspecified"))
      (node (ref "RV1") (pin "4") (pinfunction "EH_4") (pintype "unspecified"))
      (node (ref "RV1") (pin "5") (pinfunction "EH_5") (pintype "unspecified"))
      (node (ref "RV2") (pin "3") (pinfunction "3_3") (pintype "unspecified"))
      (node (ref "RV2") (pin "4") (pinfunction "EH_4") (pintype "unspecified"))
      (node (ref "RV2") (pin "5") (pinfunction "EH_5") (pintype "unspecified"))
      (node (ref "RV3") (pin "3") (pinfunction "3_3") (pintype "unspecified"))
      (node (ref "RV3") (pin "4") (pinfunction "EH_4") (pintype "unspecified"))
      (node (ref "RV3") (pin "5") (pinfunction "EH_5") (pintype "unspecified"))
      (node (ref "SW49") (pin "1") (pinfunction "1_1") (pintype "unspecified"))
      (node (ref "SW49") (pin "3") (pinfunction "3_3") (pintype "unspecified"))
      (node (ref "Screen1") (pin "1") (pinfunction "Pin_1_1") (pintype "unspecified"))
      (node (ref "U1") (pin "G1") (pinfunction "G1_G1") (pintype "unspecified"))
      (node (ref "U1") (pin "G3") (pinfunction "G3_G3") (pintype "unspecified"))
      (node (ref "U5") (pin "5") (pinfunction "GND_5") (pintype "unspecified"))
      (node (ref "U5") (pin "8") (pinfunction "VCC_8") (pintype "unspecified"))
      (node (ref "U8") (pin "1") (pinfunction "#1OE_1") (pintype "unspecified"))
      (node (ref "U8") (pin "10") (pinfunction "#3OE_10") (pintype "unspecified"))
      (node (ref "U8") (pin "11") (pinfunction "4Y_11") (pintype "unspecified"))
      (node (ref "U8") (pin "12") (pinfunction "4A_12") (pintype "unspecified"))
      (node (ref "U8") (pin "13") (pinfunction "#4OE_13") (pintype "unspecified"))
      (node (ref "U8") (pin "4") (pinfunction "#2OE_4") (pintype "unspecified"))
      (node (ref "U8") (pin "7") (pinfunction "GND_7") (pintype "unspecified"))
      (node (ref "U8") (pin "8") (pinfunction "3Y_8") (pintype "unspecified"))
      (node (ref "U8") (pin "9") (pinfunction "3A_9") (pintype "unspecified"))
    )
    (net (code "26") (name "LED") (class "Default")
      (node (ref "U1") (pin "6") (pinfunction "6_6") (pintype "bidirectional"))
      (node (ref "U8") (pin "2") (pinfunction "1A_2") (pintype "unspecified"))
    )
    (net (code "27") (name "LEDCNTRL") (class "Default")
      (node (ref "D1") (pin "4") (pinfunction "DIN_4") (pintype "input"))
      (node (ref "R20") (pin "2") (pinfunction "~_2") (pintype "unspecified"))
    )
    (net (code "28") (name "MAIN") (class "Default")
      (node (ref "COL_MUX1") (pin "18") (pinfunction "I13_18") (pintype "unspecified"))
      (node (ref "RV3") (pin "2") (pinfunction "2_2") (pintype "unspecified"))
    )
    (net (code "29") (name "MIDI_OUT") (class "Default")
      (node (ref "R19") (pin "2") (pinfunction "~_2") (pintype "unspecified"))
      (node (ref "R71") (pin "2") (pinfunction "~_2") (pintype "unspecified"))
      (node (ref "U8") (pin "6") (pinfunction "2Y_6") (pintype "unspecified"))
    )
    (net (code "30") (name "MIDI_RX") (class "Default")
      (node (ref "R2") (pin "2") (pinfunction "~_2") (pintype "unspecified"))
      (node (ref "U1") (pin "0") (pinfunction "0_0") (pintype "bidirectional"))
      (node (ref "U5") (pin "6") (pinfunction "VO2_6") (pintype "unspecified"))
    )
    (net (code "31") (name "MIDI_TX") (class "Default")
      (node (ref "U1") (pin "1") (pinfunction "1_1") (pintype "bidirectional"))
      (node (ref "U8") (pin "5") (pinfunction "2A_5") (pintype "unspecified"))
    )
    (net (code "32") (name "MRC") (class "Default")
      (node (ref "COL_MUX1") (pin "1") (pinfunction "COM_1") (pintype "unspecified"))
      (node (ref "U1") (pin "7") (pinfunction "7_7") (pintype "bidirectional"))
    )
    (net (code "33") (name "MRR") (class "Default")
      (node (ref "ROW_MUX1") (pin "1") (pinfunction "COM_1") (pintype "unspecified"))
      (node (ref "U1") (pin "22") (pinfunction "22_22") (pintype "bidirectional"))
    )
    (net (code "34") (name "MUXC1") (class "Default")
      (node (ref "COL_MUX1") (pin "10") (pinfunction "S0_10") (pintype "input"))
      (node (ref "U1") (pin "8") (pinfunction "8_8") (pintype "bidirectional"))
    )
    (net (code "35") (name "MUXC2") (class "Default")
      (node (ref "COL_MUX1") (pin "11") (pinfunction "S1_11") (pintype "input"))
      (node (ref "U1") (pin "9") (pinfunction "9_9") (pintype "bidirectional"))
    )
    (net (code "36") (name "MUXC3") (class "Default")
      (node (ref "COL_MUX1") (pin "14") (pinfunction "S2_14") (pintype "input"))
      (node (ref "U1") (pin "10") (pinfunction "10_10") (pintype "bidirectional"))
    )
    (net (code "37") (name "MUXC4") (class "Default")
      (node (ref "COL_MUX1") (pin "13") (pinfunction "S3_13") (pintype "input"))
      (node (ref "U1") (pin "11") (pinfunction "11_11") (pintype "bidirectional"))
    )
    (net (code "38") (name "MUXR1") (class "Default")
      (node (ref "ROW_MUX1") (pin "10") (pinfunction "S0_10") (pintype "input"))
      (node (ref "U1") (pin "2") (pinfunction "2_2") (pintype "bidirectional"))
    )
    (net (code "39") (name "MUXR2") (class "Default")
      (node (ref "ROW_MUX1") (pin "11") (pinfunction "S1_11") (pintype "input"))
      (node (ref "U1") (pin "3") (pinfunction "3_3") (pintype "bidirectional"))
    )
    (net (code "40") (name "MUXR3") (class "Default")
      (node (ref "ROW_MUX1") (pin "14") (pinfunction "S2_14") (pintype "input"))
      (node (ref "U1") (pin "4") (pinfunction "4_4") (pintype "bidirectional"))
    )
    (net (code "41") (name "MUXR4") (class "Default")
      (node (ref "ROW_MUX1") (pin "13") (pinfunction "S3_13") (pintype "input"))
      (node (ref "U1") (pin "5") (pinfunction "5_5") (pintype "bidirectional"))
    )
    (net (code "42") (name "Net-(C11-Pad1)") (class "Default")
      (node (ref "C11") (pin "1") (pinfunction "1_1") (pintype "input"))
      (node (ref "J4") (pin "4") (pinfunction "4_4") (pintype "unspecified"))
    )
    (net (code "43") (name "Net-(C11-Pad2)") (class "Default")
      (node (ref "C11") (pin "2") (pinfunction "2_2") (pintype "input"))
      (node (ref "R22") (pin "2") (pinfunction "~_2") (pintype "unspecified"))
      (node (ref "R23") (pin "2") (pinfunction "~_2") (pintype "unspecified"))
    )
    (net (code "44") (name "Net-(C37-~-Pad1)") (class "Default")
      (node (ref "C37") (pin "1") (pinfunction "~_1") (pintype "unspecified"))
      (node (ref "C38") (pin "1") (pinfunction "1_1") (pintype "input"))
      (node (ref "R46") (pin "1") (pinfunction "~_1") (pintype "unspecified"))
      (node (ref "U1") (pin "G2") (pinfunction "G2_G2") (pintype "unspecified"))
    )
    (net (code "45") (name "Net-(C37-~-Pad2)") (class "Default")
      (node (ref "C37") (pin "2") (pinfunction "~_2") (pintype "unspecified"))
      (node (ref "C38") (pin "2") (pinfunction "2_2") (pintype "input"))
      (node (ref "R47") (pin "1") (pinfunction "~_1") (pintype "unspecified"))
      (node (ref "U1") (pin "3.3V_1") (pinfunction "3.3V_1_3.3V_1") (pintype "unspecified"))
    )
    (net (code "46") (name "Net-(C39-Pad1)") (class "Default")
      (node (ref "C39") (pin "1") (pinfunction "1_1") (pintype "input"))
      (node (ref "J5") (pin "4") (pinfunction "4_4") (pintype "unspecified"))
    )
    (net (code "47") (name "Net-(C39-Pad2)") (class "Default")
      (node (ref "C39") (pin "2") (pinfunction "2_2") (pintype "input"))
      (node (ref "R48") (pin "2") (pinfunction "~_2") (pintype "unspecified"))
      (node (ref "R49") (pin "2") (pinfunction "~_2") (pintype "unspecified"))
    )
    (net (code "48") (name "Net-(C42-Pad1)") (class "Default")
      (node (ref "C42") (pin "1") (pinfunction "1_1") (pintype "input"))
      (node (ref "J6") (pin "4") (pinfunction "4_4") (pintype "unspecified"))
    )
    (net (code "49") (name "Net-(C42-Pad2)") (class "Default")
      (node (ref "C42") (pin "2") (pinfunction "2_2") (pintype "input"))
      (node (ref "R52") (pin "2") (pinfunction "~_2") (pintype "unspecified"))
      (node (ref "R53") (pin "2") (pinfunction "~_2") (pintype "unspecified"))
    )
    (net (code "50") (name "Net-(C45-Pad1)") (class "Default")
      (node (ref "C45") (pin "1") (pinfunction "1_1") (pintype "input"))
      (node (ref "J7") (pin "4") (pinfunction "4_4") (pintype "unspecified"))
    )
    (net (code "51") (name "Net-(C45-Pad2)") (class "Default")
      (node (ref "C45") (pin "2") (pinfunction "2_2") (pintype "input"))
      (node (ref "R56") (pin "2") (pinfunction "~_2") (pintype "unspecified"))
      (node (ref "R57") (pin "2") (pinfunction "~_2") (pintype "unspecified"))
    )
    (net (code "52") (name "Net-(C48-Pad1)") (class "Default")
      (node (ref "C48") (pin "1") (pinfunction "1_1") (pintype "input"))
      (node (ref "J8") (pin "4") (pinfunction "4_4") (pintype "unspecified"))
    )
    (net (code "53") (name "Net-(C48-Pad2)") (class "Default")
      (node (ref "C48") (pin "2") (pinfunction "2_2") (pintype "input"))
      (node (ref "R60") (pin "2") (pinfunction "~_2") (pintype "unspecified"))
      (node (ref "R61") (pin "2") (pinfunction "~_2") (pintype "unspecified"))
    )
    (net (code "54") (name "Net-(C51-Pad1)") (class "Default")
      (node (ref "C51") (pin "1") (pinfunction "1_1") (pintype "input"))
      (node (ref "J9") (pin "4") (pinfunction "4_4") (pintype "unspecified"))
    )
    (net (code "55") (name "Net-(C51-Pad2)") (class "Default")
      (node (ref "C51") (pin "2") (pinfunction "2_2") (pintype "input"))
      (node (ref "R64") (pin "2") (pinfunction "~_2") (pintype "unspecified"))
      (node (ref "R65") (pin "2") (pinfunction "~_2") (pintype "unspecified"))
    )
    (net (code "56") (name "Net-(D1-DOUT)") (class "Default")
      (node (ref "D1") (pin "2") (pinfunction "DOUT_2") (pintype "output"))
      (node (ref "D2") (pin "4") (pinfunction "DIN_4") (pintype "input"))
    )
    (net (code "57") (name "Net-(D1-VSS)") (class "Default")
      (node (ref "D1") (pin "3") (pinfunction "VSS_3") (pintype "unspecified"))
      (node (ref "D2") (pin "1") (pinfunction "VDD_1") (pintype "unspecified"))
    )
    (net (code "58") (name "Net-(D2-DOUT)") (class "Default")
      (node (ref "D2") (pin "2") (pinfunction "DOUT_2") (pintype "output"))
      (node (ref "D3") (pin "4") (pinfunction "DIN_4") (pintype "input"))
    )
    (net (code "59") (name "Net-(D2-VSS)") (class "Default")
      (node (ref "D2") (pin "3") (pinfunction "VSS_3") (pintype "unspecified"))
      (node (ref "D3") (pin "1") (pinfunction "VDD_1") (pintype "unspecified"))
    )
    (net (code "60") (name "Net-(D3-DOUT)") (class "Default")
      (node (ref "D3") (pin "2") (pinfunction "DOUT_2") (pintype "output"))
      (node (ref "D4") (pin "4") (pinfunction "DIN_4") (pintype "input"))
    )
    (net (code "61") (name "Net-(D3-VSS)") (class "Default")
      (node (ref "D3") (pin "3") (pinfunction "VSS_3") (pintype "unspecified"))
      (node (ref "D4") (pin "1") (pinfunction "VDD_1") (pintype "unspecified"))
    )
    (net (code "62") (name "Net-(D4-DOUT)") (class "Default")
      (node (ref "D4") (pin "2") (pinfunction "DOUT_2") (pintype "output"))
      (node (ref "D5") (pin "4") (pinfunction "DIN_4") (pintype "input"))
    )
    (net (code "63") (name "Net-(D4-VSS)") (class "Default")
      (node (ref "D4") (pin "3") (pinfunction "VSS_3") (pintype "unspecified"))
      (node (ref "D5") (pin "1") (pinfunction "VDD_1") (pintype "unspecified"))
    )
    (net (code "64") (name "Net-(D5-DOUT)") (class "Default")
      (node (ref "D5") (pin "2") (pinfunction "DOUT_2") (pintype "output"))
      (node (ref "D6") (pin "4") (pinfunction "DIN_4") (pintype "input"))
    )
    (net (code "65") (name "Net-(D5-VSS)") (class "Default")
      (node (ref "D5") (pin "3") (pinfunction "VSS_3") (pintype "unspecified"))
      (node (ref "D6") (pin "1") (pinfunction "VDD_1") (pintype "unspecified"))
    )
    (net (code "66") (name "Net-(D6-DOUT)") (class "Default")
      (node (ref "D6") (pin "2") (pinfunction "DOUT_2") (pintype "output"))
      (node (ref "D7") (pin "4") (pinfunction "DIN_4") (pintype "input"))
    )
    (net (code "67") (name "Net-(D6-VSS)") (class "Default")
      (node (ref "C31") (pin "1") (pinfunction "~_1") (pintype "unspecified"))
      (node (ref "D6") (pin "3") (pinfunction "VSS_3") (pintype "unspecified"))
      (node (ref "D7") (pin "1") (pinfunction "VDD_1") (pintype "unspecified"))
    )
    (net (code "68") (name "Net-(D7-DOUT)") (class "Default")
      (node (ref "D7") (pin "2") (pinfunction "DOUT_2") (pintype "output"))
      (node (ref "D8") (pin "4") (pinfunction "DIN_4") (pintype "input"))
    )
    (net (code "69") (name "Net-(D7-VSS)") (class "Default")
      (node (ref "D7") (pin "3") (pinfunction "VSS_3") (pintype "unspecified"))
      (node (ref "D8") (pin "1") (pinfunction "VDD_1") (pintype "unspecified"))
    )
    (net (code "70") (name "Net-(D8-DOUT)") (class "Default")
      (node (ref "D8") (pin "2") (pinfunction "DOUT_2") (pintype "output"))
      (node (ref "D9") (pin "4") (pinfunction "DIN_4") (pintype "input"))
    )
    (net (code "71") (name "Net-(D8-VSS)") (class "Default")
      (node (ref "D8") (pin "3") (pinfunction "VSS_3") (pintype "unspecified"))
      (node (ref "D9") (pin "1") (pinfunction "VDD_1") (pintype "unspecified"))
    )
    (net (code "72") (name "Net-(D10-DIN)") (class "Default")
      (node (ref "D10") (pin "4") (pinfunction "DIN_4") (pintype "input"))
      (node (ref "D9") (pin "2") (pinfunction "DOUT_2") (pintype "output"))
    )
    (net (code "73") (name "Net-(D10-DOUT)") (class "Default")
      (node (ref "D10") (pin "2") (pinfunction "DOUT_2") (pintype "output"))
      (node (ref "D11") (pin "4") (pinfunction "DIN_4") (pintype "input"))
    )
    (net (code "74") (name "Net-(D10-VDD)") (class "Default")
      (node (ref "D10") (pin "1") (pinfunction "VDD_1") (pintype "unspecified"))
      (node (ref "D9") (pin "3") (pinfunction "VSS_3") (pintype "unspecified"))
    )
    (net (code "75") (name "Net-(D10-VSS)") (class "Default")
      (node (ref "D10") (pin "3") (pinfunction "VSS_3") (pintype "unspecified"))
      (node (ref "D11") (pin "1") (pinfunction "VDD_1") (pintype "unspecified"))
    )
    (net (code "76") (name "Net-(D11-DOUT)") (class "Default")
      (node (ref "D11") (pin "2") (pinfunction "DOUT_2") (pintype "output"))
      (node (ref "D12") (pin "4") (pinfunction "DIN_4") (pintype "input"))
    )
    (net (code "77") (name "Net-(D11-VSS)") (class "Default")
      (node (ref "D11") (pin "3") (pinfunction "VSS_3") (pintype "unspecified"))
      (node (ref "D12") (pin "1") (pinfunction "VDD_1") (pintype "unspecified"))
    )
    (net (code "78") (name "Net-(D12-DOUT)") (class "Default")
      (node (ref "D12") (pin "2") (pinfunction "DOUT_2") (pintype "output"))
      (node (ref "D13") (pin "4") (pinfunction "DIN_4") (pintype "input"))
    )
    (net (code "79") (name "Net-(D12-VSS)") (class "Default")
      (node (ref "C32") (pin "1") (pinfunction "~_1") (pintype "unspecified"))
      (node (ref "D12") (pin "3") (pinfunction "VSS_3") (pintype "unspecified"))
      (node (ref "D13") (pin "1") (pinfunction "VDD_1") (pintype "unspecified"))
    )
    (net (code "80") (name "Net-(D13-DOUT)") (class "Default")
      (node (ref "D13") (pin "2") (pinfunction "DOUT_2") (pintype "output"))
      (node (ref "D14") (pin "4") (pinfunction "DIN_4") (pintype "input"))
    )
    (net (code "81") (name "Net-(D13-VSS)") (class "Default")
      (node (ref "D13") (pin "3") (pinfunction "VSS_3") (pintype "unspecified"))
      (node (ref "D14") (pin "1") (pinfunction "VDD_1") (pintype "unspecified"))
    )
    (net (code "82") (name "Net-(D14-DOUT)") (class "Default")
      (node (ref "D14") (pin "2") (pinfunction "DOUT_2") (pintype "output"))
      (node (ref "D15") (pin "4") (pinfunction "DIN_4") (pintype "input"))
    )
    (net (code "83") (name "Net-(D14-VSS)") (class "Default")
      (node (ref "D14") (pin "3") (pinfunction "VSS_3") (pintype "unspecified"))
      (node (ref "D15") (pin "1") (pinfunction "VDD_1") (pintype "unspecified"))
    )
    (net (code "84") (name "Net-(D15-DOUT)") (class "Default")
      (node (ref "D15") (pin "2") (pinfunction "DOUT_2") (pintype "output"))
      (node (ref "D16") (pin "4") (pinfunction "DIN_4") (pintype "input"))
    )
    (net (code "85") (name "Net-(D15-VSS)") (class "Default")
      (node (ref "D15") (pin "3") (pinfunction "VSS_3") (pintype "unspecified"))
      (node (ref "D16") (pin "1") (pinfunction "VDD_1") (pintype "unspecified"))
    )
    (net (code "86") (name "Net-(D16-DOUT)") (class "Default")
      (node (ref "D16") (pin "2") (pinfunction "DOUT_2") (pintype "output"))
      (node (ref "D17") (pin "4") (pinfunction "DIN_4") (pintype "input"))
    )
    (net (code "87") (name "Net-(D16-VSS)") (class "Default")
      (node (ref "D16") (pin "3") (pinfunction "VSS_3") (pintype "unspecified"))
      (node (ref "D17") (pin "1") (pinfunction "VDD_1") (pintype "unspecified"))
    )
    (net (code "88") (name "Net-(D17-DOUT)") (class "Default")
      (node (ref "D17") (pin "2") (pinfunction "DOUT_2") (pintype "output"))
      (node (ref "D18") (pin "4") (pinfunction "DIN_4") (pintype "input"))
    )
    (net (code "89") (name "Net-(D17-VSS)") (class "Default")
      (node (ref "D17") (pin "3") (pinfunction "VSS_3") (pintype "unspecified"))
      (node (ref "D18") (pin "1") (pinfunction "VDD_1") (pintype "unspecified"))
    )
    (net (code "90") (name "Net-(D18-DOUT)") (class "Default")
      (node (ref "D18") (pin "2") (pinfunction "DOUT_2") (pintype "output"))
      (node (ref "D19") (pin "4") (pinfunction "DIN_4") (pintype "input"))
    )
    (net (code "91") (name "Net-(D18-VSS)") (class "Default")
      (node (ref "C33") (pin "1") (pinfunction "~_1") (pintype "unspecified"))
      (node (ref "D18") (pin "3") (pinfunction "VSS_3") (pintype "unspecified"))
      (node (ref "D19") (pin "1") (pinfunction "VDD_1") (pintype "unspecified"))
    )
    (net (code "92") (name "Net-(D19-DOUT)") (class "Default")
      (node (ref "D19") (pin "2") (pinfunction "DOUT_2") (pintype "output"))
      (node (ref "D20") (pin "4") (pinfunction "DIN_4") (pintype "input"))
    )
    (net (code "93") (name "Net-(D19-VSS)") (class "Default")
      (node (ref "D19") (pin "3") (pinfunction "VSS_3") (pintype "unspecified"))
      (node (ref "D20") (pin "1") (pinfunction "VDD_1") (pintype "unspecified"))
    )
    (net (code "94") (name "Net-(D20-DOUT)") (class "Default")
      (node (ref "D20") (pin "2") (pinfunction "DOUT_2") (pintype "output"))
      (node (ref "D21") (pin "4") (pinfunction "DIN_4") (pintype "input"))
    )
    (net (code "95") (name "Net-(D20-VSS)") (class "Default")
      (node (ref "D20") (pin "3") (pinfunction "VSS_3") (pintype "unspecified"))
      (node (ref "D21") (pin "1") (pinfunction "VDD_1") (pintype "unspecified"))
    )
    (net (code "96") (name "Net-(D21-DOUT)") (class "Default")
      (node (ref "D21") (pin "2") (pinfunction "DOUT_2") (pintype "output"))
      (node (ref "D22") (pin "4") (pinfunction "DIN_4") (pintype "input"))
    )
    (net (code "97") (name "Net-(D21-VSS)") (class "Default")
      (node (ref "D21") (pin "3") (pinfunction "VSS_3") (pintype "unspecified"))
      (node (ref "D22") (pin "1") (pinfunction "VDD_1") (pintype "unspecified"))
    )
    (net (code "98") (name "Net-(D22-DOUT)") (class "Default")
      (node (ref "D22") (pin "2") (pinfunction "DOUT_2") (pintype "output"))
      (node (ref "D23") (pin "4") (pinfunction "DIN_4") (pintype "input"))
    )
    (net (code "99") (name "Net-(D22-VSS)") (class "Default")
      (node (ref "D22") (pin "3") (pinfunction "VSS_3") (pintype "unspecified"))
      (node (ref "D23") (pin "1") (pinfunction "VDD_1") (pintype "unspecified"))
    )
    (net (code "100") (name "Net-(D23-DOUT)") (class "Default")
      (node (ref "D23") (pin "2") (pinfunction "DOUT_2") (pintype "output"))
      (node (ref "D24") (pin "4") (pinfunction "DIN_4") (pintype "input"))
    )
    (net (code "101") (name "Net-(D23-VSS)") (class "Default")
      (node (ref "D23") (pin "3") (pinfunction "VSS_3") (pintype "unspecified"))
      (node (ref "D24") (pin "1") (pinfunction "VDD_1") (pintype "unspecified"))
    )
    (net (code "102") (name "Net-(D24-DOUT)") (class "Default")
      (node (ref "D24") (pin "2") (pinfunction "DOUT_2") (pintype "output"))
      (node (ref "D25") (pin "4") (pinfunction "DIN_4") (pintype "input"))
    )
    (net (code "103") (name "Net-(D24-VSS)") (class "Default")
      (node (ref "C34") (pin "1") (pinfunction "~_1") (pintype "unspecified"))
      (node (ref "D24") (pin "3") (pinfunction "VSS_3") (pintype "unspecified"))
      (node (ref "D25") (pin "1") (pinfunction "VDD_1") (pintype "unspecified"))
    )
    (net (code "104") (name "Net-(D25-DOUT)") (class "Default")
      (node (ref "D25") (pin "2") (pinfunction "DOUT_2") (pintype "output"))
      (node (ref "D26") (pin "4") (pinfunction "DIN_4") (pintype "input"))
    )
    (net (code "105") (name "Net-(D25-VSS)") (class "Default")
      (node (ref "D25") (pin "3") (pinfunction "VSS_3") (pintype "unspecified"))
      (node (ref "D26") (pin "1") (pinfunction "VDD_1") (pintype "unspecified"))
    )
    (net (code "106") (name "Net-(D26-DOUT)") (class "Default")
      (node (ref "D26") (pin "2") (pinfunction "DOUT_2") (pintype "output"))
      (node (ref "D27") (pin "4") (pinfunction "DIN_4") (pintype "input"))
    )
    (net (code "107") (name "Net-(D26-VSS)") (class "Default")
      (node (ref "D26") (pin "3") (pinfunction "VSS_3") (pintype "unspecified"))
      (node (ref "D27") (pin "1") (pinfunction "VDD_1") (pintype "unspecified"))
    )
    (net (code "108") (name "Net-(D27-DOUT)") (class "Default")
      (node (ref "D27") (pin "2") (pinfunction "DOUT_2") (pintype "output"))
      (node (ref "D28") (pin "4") (pinfunction "DIN_4") (pintype "input"))
    )
    (net (code "109") (name "Net-(D27-VSS)") (class "Default")
      (node (ref "D27") (pin "3") (pinfunction "VSS_3") (pintype "unspecified"))
      (node (ref "D28") (pin "1") (pinfunction "VDD_1") (pintype "unspecified"))
    )
    (net (code "110") (name "Net-(D28-DOUT)") (class "Default")
      (node (ref "D28") (pin "2") (pinfunction "DOUT_2") (pintype "output"))
      (node (ref "D29") (pin "4") (pinfunction "DIN_4") (pintype "input"))
    )
    (net (code "111") (name "Net-(D28-VSS)") (class "Default")
      (node (ref "D28") (pin "3") (pinfunction "VSS_3") (pintype "unspecified"))
      (node (ref "D29") (pin "1") (pinfunction "VDD_1") (pintype "unspecified"))
    )
    (net (code "112") (name "Net-(D29-DOUT)") (class "Default")
      (node (ref "D29") (pin "2") (pinfunction "DOUT_2") (pintype "output"))
      (node (ref "D30") (pin "4") (pinfunction "DIN_4") (pintype "input"))
    )
    (net (code "113") (name "Net-(D29-VSS)") (class "Default")
      (node (ref "D29") (pin "3") (pinfunction "VSS_3") (pintype "unspecified"))
      (node (ref "D30") (pin "1") (pinfunction "VDD_1") (pintype "unspecified"))
    )
    (net (code "114") (name "Net-(D30-DOUT)") (class "Default")
      (node (ref "D30") (pin "2") (pinfunction "DOUT_2") (pintype "output"))
      (node (ref "D31") (pin "4") (pinfunction "DIN_4") (pintype "input"))
    )
    (net (code "115") (name "Net-(D30-VSS)") (class "Default")
      (node (ref "C35") (pin "1") (pinfunction "~_1") (pintype "unspecified"))
      (node (ref "D30") (pin "3") (pinfunction "VSS_3") (pintype "unspecified"))
      (node (ref "D31") (pin "1") (pinfunction "VDD_1") (pintype "unspecified"))
    )
    (net (code "116") (name "Net-(D31-DOUT)") (class "Default")
      (node (ref "D31") (pin "2") (pinfunction "DOUT_2") (pintype "output"))
      (node (ref "D32") (pin "4") (pinfunction "DIN_4") (pintype "input"))
    )
    (net (code "117") (name "Net-(D31-VSS)") (class "Default")
      (node (ref "D31") (pin "3") (pinfunction "VSS_3") (pintype "unspecified"))
      (node (ref "D32") (pin "1") (pinfunction "VDD_1") (pintype "unspecified"))
    )
    (net (code "118") (name "Net-(D32-DOUT)") (class "Default")
      (node (ref "D32") (pin "2") (pinfunction "DOUT_2") (pintype "output"))
      (node (ref "D33") (pin "4") (pinfunction "DIN_4") (pintype "input"))
    )
    (net (code "119") (name "Net-(D32-VSS)") (class "Default")
      (node (ref "D32") (pin "3") (pinfunction "VSS_3") (pintype "unspecified"))
      (node (ref "D33") (pin "1") (pinfunction "VDD_1") (pintype "unspecified"))
    )
    (net (code "120") (name "Net-(D33-DOUT)") (class "Default")
      (node (ref "D33") (pin "2") (pinfunction "DOUT_2") (pintype "output"))
      (node (ref "D34") (pin "4") (pinfunction "DIN_4") (pintype "input"))
    )
    (net (code "121") (name "Net-(D33-VSS)") (class "Default")
      (node (ref "D33") (pin "3") (pinfunction "VSS_3") (pintype "unspecified"))
      (node (ref "D34") (pin "1") (pinfunction "VDD_1") (pintype "unspecified"))
    )
    (net (code "122") (name "Net-(D34-DOUT)") (class "Default")
      (node (ref "D34") (pin "2") (pinfunction "DOUT_2") (pintype "output"))
      (node (ref "D35") (pin "4") (pinfunction "DIN_4") (pintype "input"))
    )
    (net (code "123") (name "Net-(D34-VSS)") (class "Default")
      (node (ref "D34") (pin "3") (pinfunction "VSS_3") (pintype "unspecified"))
      (node (ref "D35") (pin "1") (pinfunction "VDD_1") (pintype "unspecified"))
    )
    (net (code "124") (name "Net-(D35-DOUT)") (class "Default")
      (node (ref "D35") (pin "2") (pinfunction "DOUT_2") (pintype "output"))
      (node (ref "D36") (pin "4") (pinfunction "DIN_4") (pintype "input"))
    )
    (net (code "125") (name "Net-(D35-VSS)") (class "Default")
      (node (ref "D35") (pin "3") (pinfunction "VSS_3") (pintype "unspecified"))
      (node (ref "D36") (pin "1") (pinfunction "VDD_1") (pintype "unspecified"))
    )
    (net (code "126") (name "Net-(D36-DOUT)") (class "Default")
      (node (ref "D36") (pin "2") (pinfunction "DOUT_2") (pintype "output"))
      (node (ref "D37") (pin "4") (pinfunction "DIN_4") (pintype "input"))
    )
    (net (code "127") (name "Net-(D36-VSS)") (class "Default")
      (node (ref "C36") (pin "1") (pinfunction "~_1") (pintype "unspecified"))
      (node (ref "D36") (pin "3") (pinfunction "VSS_3") (pintype "unspecified"))
      (node (ref "D37") (pin "1") (pinfunction "VDD_1") (pintype "unspecified"))
    )
    (net (code "128") (name "Net-(D37-DOUT)") (class "Default")
      (node (ref "D37") (pin "2") (pinfunction "DOUT_2") (pintype "output"))
      (node (ref "D38") (pin "4") (pinfunction "DIN_4") (pintype "input"))
    )
    (net (code "129") (name "Net-(D37-VSS)") (class "Default")
      (node (ref "D37") (pin "3") (pinfunction "VSS_3") (pintype "unspecified"))
      (node (ref "D38") (pin "1") (pinfunction "VDD_1") (pintype "unspecified"))
    )
    (net (code "130") (name "Net-(D38-DOUT)") (class "Default")
      (node (ref "D38") (pin "2") (pinfunction "DOUT_2") (pintype "output"))
      (node (ref "D39") (pin "4") (pinfunction "DIN_4") (pintype "input"))
    )
    (net (code "131") (name "Net-(D38-VSS)") (class "Default")
      (node (ref "D38") (pin "3") (pinfunction "VSS_3") (pintype "unspecified"))
      (node (ref "D39") (pin "1") (pinfunction "VDD_1") (pintype "unspecified"))
    )
    (net (code "132") (name "Net-(D39-DOUT)") (class "Default")
      (node (ref "D39") (pin "2") (pinfunction "DOUT_2") (pintype "output"))
      (node (ref "D40") (pin "4") (pinfunction "DIN_4") (pintype "input"))
    )
    (net (code "133") (name "Net-(D39-VSS)") (class "Default")
      (node (ref "D39") (pin "3") (pinfunction "VSS_3") (pintype "unspecified"))
      (node (ref "D40") (pin "1") (pinfunction "VDD_1") (pintype "unspecified"))
    )
    (net (code "134") (name "Net-(D40-DOUT)") (class "Default")
      (node (ref "D40") (pin "2") (pinfunction "DOUT_2") (pintype "output"))
      (node (ref "D41") (pin "4") (pinfunction "DIN_4") (pintype "input"))
    )
    (net (code "135") (name "Net-(D40-VSS)") (class "Default")
      (node (ref "D40") (pin "3") (pinfunction "VSS_3") (pintype "unspecified"))
      (node (ref "D41") (pin "1") (pinfunction "VDD_1") (pintype "unspecified"))
    )
    (net (code "136") (name "Net-(D41-DOUT)") (class "Default")
      (node (ref "D41") (pin "2") (pinfunction "DOUT_2") (pintype "output"))
      (node (ref "D42") (pin "4") (pinfunction "DIN_4") (pintype "input"))
    )
    (net (code "137") (name "Net-(D41-VSS)") (class "Default")
      (node (ref "D41") (pin "3") (pinfunction "VSS_3") (pintype "unspecified"))
      (node (ref "D42") (pin "1") (pinfunction "VDD_1") (pintype "unspecified"))
    )
    (net (code "138") (name "Net-(D43-A)") (class "Default")
      (node (ref "D43") (pin "2") (pinfunction "A_2") (pintype "unspecified"))
      (node (ref "R21") (pin "1") (pinfunction "~_1") (pintype "unspecified"))
      (node (ref "U5") (pin "3") (pinfunction "C2_3") (pintype "unspecified"))
    )
    (net (code "139") (name "Net-(D43-K)") (class "Default")
      (node (ref "D43") (pin "1") (pinfunction "K_1") (pintype "unspecified"))
      (node (ref "J10") (pin "2") (pinfunction "2_2") (pintype "unspecified"))
      (node (ref "J2") (pin "4") (pinfunction "4_4") (pintype "unspecified"))
      (node (ref "U5") (pin "2") (pinfunction "C1_2") (pintype "unspecified"))
    )
    (net (code "140") (name "Net-(D45-A)") (class "Default")
      (node (ref "D45") (pin "2") (pinfunction "A_2") (pintype "unspecified"))
      (node (ref "R24") (pin "1") (pinfunction "~_1") (pintype "unspecified"))
      (node (ref "R25") (pin "1") (pinfunction "~_1") (pintype "unspecified"))
      (node (ref "U21") (pin "1") (pinfunction "OUTA_1") (pintype "output"))
    )
    (net (code "141") (name "Net-(D45-K)") (class "Default")
      (node (ref "D45") (pin "1") (pinfunction "K_1") (pintype "unspecified"))
      (node (ref "R23") (pin "1") (pinfunction "~_1") (pintype "unspecified"))
      (node (ref "U21") (pin "2") (pinfunction "INA-_2") (pintype "unspecified"))
    )
    (net (code "142") (name "Net-(D46-A)") (class "Default")
      (node (ref "D46") (pin "2") (pinfunction "A_2") (pintype "unspecified"))
      (node (ref "R50") (pin "1") (pinfunction "~_1") (pintype "unspecified"))
      (node (ref "R51") (pin "1") (pinfunction "~_1") (pintype "unspecified"))
      (node (ref "U22") (pin "7") (pinfunction "OUTB_7") (pintype "output"))
    )
    (net (code "143") (name "Net-(D46-K)") (class "Default")
      (node (ref "D46") (pin "1") (pinfunction "K_1") (pintype "unspecified"))
      (node (ref "R49") (pin "1") (pinfunction "~_1") (pintype "unspecified"))
      (node (ref "U22") (pin "6") (pinfunction "INB-_6") (pintype "unspecified"))
    )
    (net (code "144") (name "Net-(D47-A)") (class "Default")
      (node (ref "D47") (pin "2") (pinfunction "A_2") (pintype "unspecified"))
      (node (ref "R54") (pin "1") (pinfunction "~_1") (pintype "unspecified"))
      (node (ref "R55") (pin "1") (pinfunction "~_1") (pintype "unspecified"))
      (node (ref "U21") (pin "7") (pinfunction "OUTB_7") (pintype "output"))
    )
    (net (code "145") (name "Net-(D47-K)") (class "Default")
      (node (ref "D47") (pin "1") (pinfunction "K_1") (pintype "unspecified"))
      (node (ref "R53") (pin "1") (pinfunction "~_1") (pintype "unspecified"))
      (node (ref "U21") (pin "6") (pinfunction "INB-_6") (pintype "unspecified"))
    )
    (net (code "146") (name "Net-(D48-A)") (class "Default")
      (node (ref "D48") (pin "2") (pinfunction "A_2") (pintype "unspecified"))
      (node (ref "R58") (pin "1") (pinfunction "~_1") (pintype "unspecified"))
      (node (ref "R59") (pin "1") (pinfunction "~_1") (pintype "unspecified"))
      (node (ref "U22") (pin "1") (pinfunction "OUTA_1") (pintype "output"))
    )
    (net (code "147") (name "Net-(D48-K)") (class "Default")
      (node (ref "D48") (pin "1") (pinfunction "K_1") (pintype "unspecified"))
      (node (ref "R57") (pin "1") (pinfunction "~_1") (pintype "unspecified"))
      (node (ref "U22") (pin "2") (pinfunction "INA-_2") (pintype "unspecified"))
    )
    (net (code "148") (name "Net-(D49-A)") (class "Default")
      (node (ref "D49") (pin "2") (pinfunction "A_2") (pintype "unspecified"))
      (node (ref "R62") (pin "1") (pinfunction "~_1") (pintype "unspecified"))
      (node (ref "R63") (pin "1") (pinfunction "~_1") (pintype "unspecified"))
      (node (ref "U23") (pin "1") (pinfunction "OUTA_1") (pintype "output"))
    )
    (net (code "149") (name "Net-(D49-K)") (class "Default")
      (node (ref "D49") (pin "1") (pinfunction "K_1") (pintype "unspecified"))
      (node (ref "R61") (pin "1") (pinfunction "~_1") (pintype "unspecified"))
      (node (ref "U23") (pin "2") (pinfunction "INA-_2") (pintype "unspecified"))
    )
    (net (code "150") (name "Net-(D50-A)") (class "Default")
      (node (ref "D50") (pin "2") (pinfunction "A_2") (pintype "unspecified"))
      (node (ref "R66") (pin "1") (pinfunction "~_1") (pintype "unspecified"))
      (node (ref "R67") (pin "1") (pinfunction "~_1") (pintype "unspecified"))
      (node (ref "U23") (pin "7") (pinfunction "OUTB_7") (pintype "output"))
    )
    (net (code "151") (name "Net-(D50-K)") (class "Default")
      (node (ref "D50") (pin "1") (pinfunction "K_1") (pintype "unspecified"))
      (node (ref "R65") (pin "1") (pinfunction "~_1") (pintype "unspecified"))
      (node (ref "U23") (pin "6") (pinfunction "INB-_6") (pintype "unspecified"))
    )
    (net (code "152") (name "Net-(D51-DOUT)") (class "Default")
      (node (ref "D51") (pin "2") (pinfunction "DOUT_2") (pintype "output"))
      (node (ref "D52") (pin "4") (pinfunction "DIN_4") (pintype "input"))
    )
    (net (code "153") (name "Net-(D51-VSS)") (class "Default")
      (node (ref "D51") (pin "3") (pinfunction "VSS_3") (pintype "unspecified"))
      (node (ref "D52") (pin "1") (pinfunction "VDD_1") (pintype "unspecified"))
    )
    (net (code "154") (name "Net-(D52-DOUT)") (class "Default")
      (node (ref "D52") (pin "2") (pinfunction "DOUT_2") (pintype "output"))
      (node (ref "D53") (pin "4") (pinfunction "DIN_4") (pintype "input"))
    )
    (net (code "155") (name "Net-(D52-VSS)") (class "Default")
      (node (ref "D52") (pin "3") (pinfunction "VSS_3") (pintype "unspecified"))
      (node (ref "D53") (pin "1") (pinfunction "VDD_1") (pintype "unspecified"))
    )
    (net (code "156") (name "Net-(D53-DOUT)") (class "Default")
      (node (ref "D53") (pin "2") (pinfunction "DOUT_2") (pintype "output"))
      (node (ref "D54") (pin "4") (pinfunction "DIN_4") (pintype "input"))
    )
    (net (code "157") (name "Net-(D53-VSS)") (class "Default")
      (node (ref "D53") (pin "3") (pinfunction "VSS_3") (pintype "unspecified"))
      (node (ref "D54") (pin "1") (pinfunction "VDD_1") (pintype "unspecified"))
    )
    (net (code "158") (name "Net-(D54-DOUT)") (class "Default")
      (node (ref "D54") (pin "2") (pinfunction "DOUT_2") (pintype "output"))
      (node (ref "D55") (pin "4") (pinfunction "DIN_4") (pintype "input"))
    )
    (net (code "159") (name "Net-(D54-VSS)") (class "Default")
      (node (ref "D54") (pin "3") (pinfunction "VSS_3") (pintype "unspecified"))
      (node (ref "D55") (pin "1") (pinfunction "VDD_1") (pintype "unspecified"))
    )
    (net (code "160") (name "Net-(D55-DOUT)") (class "Default")
      (node (ref "D55") (pin "2") (pinfunction "DOUT_2") (pintype "output"))
      (node (ref "D56") (pin "4") (pinfunction "DIN_4") (pintype "input"))
    )
    (net (code "161") (name "Net-(D55-VSS)") (class "Default")
      (node (ref "D55") (pin "3") (pinfunction "VSS_3") (pintype "unspecified"))
      (node (ref "D56") (pin "1") (pinfunction "VDD_1") (pintype "unspecified"))
    )
    (net (code "162") (name "Net-(D56-DOUT)") (class "Default")
      (node (ref "D56") (pin "2") (pinfunction "DOUT_2") (pintype "output"))
      (node (ref "D57") (pin "4") (pinfunction "DIN_4") (pintype "input"))
    )
    (net (code "163") (name "Net-(D57-DOUT)") (class "Default")
      (node (ref "D57") (pin "2") (pinfunction "DOUT_2") (pintype "output"))
      (node (ref "D60") (pin "4") (pinfunction "DIN_4") (pintype "input"))
    )
    (net (code "164") (name "Net-(D57-VSS)") (class "Default")
      (node (ref "D57") (pin "3") (pinfunction "VSS_3") (pintype "unspecified"))
      (node (ref "D60") (pin "1") (pinfunction "VDD_1") (pintype "unspecified"))
    )
    (net (code "165") (name "Net-(D58-DIN)") (class "Default")
      (node (ref "D58") (pin "4") (pinfunction "DIN_4") (pintype "input"))
      (node (ref "D59") (pin "2") (pinfunction "DOUT_2") (pintype "output"))
    )
    (net (code "166") (name "Net-(D58-VDD)") (class "Default")
      (node (ref "D58") (pin "1") (pinfunction "VDD_1") (pintype "unspecified"))
      (node (ref "D59") (pin "3") (pinfunction "VSS_3") (pintype "unspecified"))
    )
    (net (code "167") (name "Net-(D59-DIN)") (class "Default")
      (node (ref "D59") (pin "4") (pinfunction "DIN_4") (pintype "input"))
      (node (ref "D60") (pin "2") (pinfunction "DOUT_2") (pintype "output"))
    )
    (net (code "168") (name "Net-(D59-VDD)") (class "Default")
      (node (ref "D59") (pin "1") (pinfunction "VDD_1") (pintype "unspecified"))
      (node (ref "D60") (pin "3") (pinfunction "VSS_3") (pintype "unspecified"))
    )
    (net (code "169") (name "Net-(J3-Pad4)") (class "Default")
      (node (ref "J3") (pin "4") (pinfunction "4_4") (pintype "unspecified"))
      (node (ref "R4") (pin "1") (pinfunction "~_1") (pintype "unspecified"))
    )
    (net (code "170") (name "Net-(J3-Pad5)") (class "Default")
      (node (ref "J3") (pin "5") (pinfunction "5_5") (pintype "unspecified"))
      (node (ref "R19") (pin "1") (pinfunction "~_1") (pintype "unspecified"))
    )
    (net (code "171") (name "Net-(J10-Pad4)") (class "Default")
      (node (ref "J10") (pin "4") (pinfunction "4_4") (pintype "unspecified"))
      (node (ref "J2") (pin "5") (pinfunction "5_5") (pintype "unspecified"))
      (node (ref "R21") (pin "2") (pinfunction "~_2") (pintype "unspecified"))
    )
    (net (code "172") (name "Net-(J11-Pad2)") (class "Default")
      (node (ref "J11") (pin "2") (pinfunction "2_2") (pintype "unspecified"))
      (node (ref "R70") (pin "1") (pinfunction "~_1") (pintype "unspecified"))
    )
    (net (code "173") (name "Net-(J11-Pad4)") (class "Default")
      (node (ref "J11") (pin "4") (pinfunction "4_4") (pintype "unspecified"))
      (node (ref "R71") (pin "1") (pinfunction "~_1") (pintype "unspecified"))
    )
    (net (code "174") (name "Net-(LEDPWR1-A)") (class "Default")
      (node (ref "LEDPWR1") (pin "2") (pinfunction "A_2") (pintype "input"))
      (node (ref "U1") (pin "23") (pinfunction "23_23") (pintype "bidirectional"))
    )
    (net (code "175") (name "Net-(U8-1Y)") (class "Default")
      (node (ref "R20") (pin "1") (pinfunction "~_1") (pintype "unspecified"))
      (node (ref "U8") (pin "3") (pinfunction "1Y_3") (pintype "unspecified"))
    )
    (net (code "176") (name "Net-(U21A-VSS)") (class "Default")
      (node (ref "C25") (pin "1") (pinfunction "1_1") (pintype "unspecified"))
      (node (ref "U21") (pin "4") (pinfunction "VSS_4") (pintype "unspecified"))
    )
    (net (code "177") (name "Net-(U22A-VDD)") (class "Default")
      (node (ref "C47") (pin "2") (pinfunction "2_2") (pintype "unspecified"))
      (node (ref "U22") (pin "8") (pinfunction "VDD_8") (pintype "unspecified"))
    )
    (net (code "178") (name "Net-(U22A-VSS)") (class "Default")
      (node (ref "C47") (pin "1") (pinfunction "1_1") (pintype "unspecified"))
      (node (ref "U22") (pin "4") (pinfunction "VSS_4") (pintype "unspecified"))
    )
    (net (code "179") (name "Net-(U23A-VDD)") (class "Default")
      (node (ref "C50") (pin "2") (pinfunction "2_2") (pintype "unspecified"))
      (node (ref "U23") (pin "8") (pinfunction "VDD_8") (pintype "unspecified"))
    )
    (net (code "180") (name "Net-(U23A-VSS)") (class "Default")
      (node (ref "C50") (pin "1") (pinfunction "1_1") (pintype "unspecified"))
      (node (ref "U23") (pin "4") (pinfunction "VSS_4") (pintype "unspecified"))
    )
    (net (code "181") (name "ROW1") (class "Default")
      (node (ref "ROW_MUX1") (pin "9") (pinfunction "I0_9") (pintype "unspecified"))
      (node (ref "SW1") (pin "1") (pinfunction "1_1") (pintype "unspecified"))
      (node (ref "SW15") (pin "1") (pinfunction "1_1") (pintype "unspecified"))
      (node (ref "SW22") (pin "1") (pinfunction "1_1") (pintype "unspecified"))
      (node (ref "SW29") (pin "1") (pinfunction "1_1") (pintype "unspecified"))
      (node (ref "SW36") (pin "1") (pinfunction "1_1") (pintype "unspecified"))
      (node (ref "SW8") (pin "1") (pinfunction "1_1") (pintype "unspecified"))
    )
    (net (code "182") (name "ROW2") (class "Default")
      (node (ref "ROW_MUX1") (pin "8") (pinfunction "I1_8") (pintype "unspecified"))
      (node (ref "SW16") (pin "1") (pinfunction "1_1") (pintype "unspecified"))
      (node (ref "SW2") (pin "1") (pinfunction "1_1") (pintype "unspecified"))
      (node (ref "SW23") (pin "1") (pinfunction "1_1") (pintype "unspecified"))
      (node (ref "SW30") (pin "1") (pinfunction "1_1") (pintype "unspecified"))
      (node (ref "SW37") (pin "1") (pinfunction "1_1") (pintype "unspecified"))
      (node (ref "SW9") (pin "1") (pinfunction "1_1") (pintype "unspecified"))
    )
    (net (code "183") (name "ROW3") (class "Default")
      (node (ref "ROW_MUX1") (pin "7") (pinfunction "I2_7") (pintype "unspecified"))
      (node (ref "SW10") (pin "1") (pinfunction "1_1") (pintype "unspecified"))
      (node (ref "SW17") (pin "1") (pinfunction "1_1") (pintype "unspecified"))
      (node (ref "SW24") (pin "1") (pinfunction "1_1") (pintype "unspecified"))
      (node (ref "SW3") (pin "1") (pinfunction "1_1") (pintype "unspecified"))
      (node (ref "SW31") (pin "1") (pinfunction "1_1") (pintype "unspecified"))
      (node (ref "SW38") (pin "1") (pinfunction "1_1") (pintype "unspecified"))
    )
    (net (code "184") (name "ROW4") (class "Default")
      (node (ref "ROW_MUX1") (pin "6") (pinfunction "I3_6") (pintype "unspecified"))
      (node (ref "SW11") (pin "1") (pinfunction "1_1") (pintype "unspecified"))
      (node (ref "SW18") (pin "1") (pinfunction "1_1") (pintype "unspecified"))
      (node (ref "SW25") (pin "1") (pinfunction "1_1") (pintype "unspecified"))
      (node (ref "SW32") (pin "1") (pinfunction "1_1") (pintype "unspecified"))
      (node (ref "SW39") (pin "1") (pinfunction "1_1") (pintype "unspecified"))
      (node (ref "SW4") (pin "1") (pinfunction "1_1") (pintype "unspecified"))
    )
    (net (code "185") (name "ROW5") (class "Default")
      (node (ref "ROW_MUX1") (pin "4") (pinfunction "I5_4") (pintype "unspecified"))
      (node (ref "ROW_MUX1") (pin "5") (pinfunction "I4_5") (pintype "unspecified"))
      (node (ref "SW12") (pin "1") (pinfunction "1_1") (pintype "unspecified"))
      (node (ref "SW19") (pin "1") (pinfunction "1_1") (pintype "unspecified"))
      (node (ref "SW26") (pin "1") (pinfunction "1_1") (pintype "unspecified"))
      (node (ref "SW33") (pin "1") (pinfunction "1_1") (pintype "unspecified"))
      (node (ref "SW40") (pin "1") (pinfunction "1_1") (pintype "unspecified"))
      (node (ref "SW5") (pin "1") (pinfunction "1_1") (pintype "unspecified"))
    )
    (net (code "186") (name "ROW6") (class "Default")
      (node (ref "ROW_MUX1") (pin "3") (pinfunction "I6_3") (pintype "unspecified"))
      (node (ref "SW13") (pin "1") (pinfunction "1_1") (pintype "unspecified"))
      (node (ref "SW20") (pin "1") (pinfunction "1_1") (pintype "unspecified"))
      (node (ref "SW27") (pin "1") (pinfunction "1_1") (pintype "unspecified"))
      (node (ref "SW34") (pin "1") (pinfunction "1_1") (pintype "unspecified"))
      (node (ref "SW41") (pin "1") (pinfunction "1_1") (pintype "unspecified"))
      (node (ref "SW6") (pin "1") (pinfunction "1_1") (pintype "unspecified"))
    )
    (net (code "187") (name "ROW7") (class "Default")
      (node (ref "ROW_MUX1") (pin "2") (pinfunction "I7_2") (pintype "unspecified"))
      (node (ref "SW14") (pin "1") (pinfunction "1_1") (pintype "unspecified"))
      (node (ref "SW21") (pin "1") (pinfunction "1_1") (pintype "unspecified"))
      (node (ref "SW28") (pin "1") (pinfunction "1_1") (pintype "unspecified"))
      (node (ref "SW35") (pin "1") (pinfunction "1_1") (pintype "unspecified"))
      (node (ref "SW42") (pin "1") (pinfunction "1_1") (pintype "unspecified"))
      (node (ref "SW7") (pin "1") (pinfunction "1_1") (pintype "unspecified"))
    )
    (net (code "188") (name "SCL") (class "Default")
      (node (ref "R68") (pin "1") (pinfunction "~_1") (pintype "unspecified"))
      (node (ref "R69") (pin "2") (pinfunction "~_2") (pintype "unspecified"))
      (node (ref "Screen1") (pin "3") (pinfunction "Pin_3_3") (pintype "unspecified"))
      (node (ref "U1") (pin "19") (pinfunction "19_19") (pintype "bidirectional"))
    )
    (net (code "189") (name "SDA") (class "Default")
      (node (ref "R68") (pin "2") (pinfunction "~_2") (pintype "unspecified"))
      (node (ref "Screen1") (pin "4") (pinfunction "Pin_4_4") (pintype "unspecified"))
      (node (ref "U1") (pin "18") (pinfunction "18_18") (pintype "bidirectional"))
    )
    (net (code "190") (name "TPWR") (class "Default")
      (node (ref "SW49") (pin "2") (pinfunction "2_2") (pintype "unspecified"))
      (node (ref "U1") (pin "VIN") (pinfunction "VIN_VIN") (pintype "unspecified"))
    )
    (net (code "191") (name "VIN_FUSED") (class "Default")
      (node (ref "C5") (pin "2") (pinfunction "2_2") (pintype "input"))
      (node (ref "C6") (pin "2") (pinfunction "2_2") (pintype "unspecified"))
      (node (ref "D44") (pin "1") (pinfunction "K_1") (pintype "input"))
      (node (ref "F1") (pin "2") (pinfunction "2_2") (pintype "unspecified"))
      (node (ref "SW49") (pin "4") (pinfunction "4_4") (pintype "unspecified"))
      (node (ref "SW49") (pin "6") (pinfunction "6_6") (pintype "unspecified"))
      (node (ref "U6") (pin "1") (pinfunction "1_1") (pintype "unspecified"))
    )
    (net (code "192") (name "VIN_RAW") (class "Default")
      (node (ref "F1") (pin "1") (pinfunction "1_1") (pintype "unspecified"))
      (node (ref "J1") (pin "1") (pinfunction "1_1") (pintype "unspecified"))
    )
    (net (code "193") (name "VLED") (class "Default")
      (node (ref "C2") (pin "1") (pinfunction "~_1") (pintype "unspecified"))
      (node (ref "C59") (pin "1") (pinfunction "~_1") (pintype "unspecified"))
      (node (ref "C7") (pin "2") (pinfunction "2_2") (pintype "unspecified"))
      (node (ref "D1") (pin "1") (pinfunction "VDD_1") (pintype "unspecified"))
      (node (ref "D57") (pin "1") (pinfunction "VDD_1") (pintype "unspecified"))
      (node (ref "U6") (pin "2") (pinfunction "2_2") (pintype "unspecified"))
    )
    (net (code "194") (name "VREF") (class "Default")
      (node (ref "R46") (pin "2") (pinfunction "~_2") (pintype "unspecified"))
      (node (ref "R47") (pin "2") (pinfunction "~_2") (pintype "unspecified"))
      (node (ref "U21") (pin "3") (pinfunction "INA+_3") (pintype "unspecified"))
      (node (ref "U21") (pin "5") (pinfunction "INB+_5") (pintype "unspecified"))
      (node (ref "U22") (pin "3") (pinfunction "INA+_3") (pintype "unspecified"))
      (node (ref "U22") (pin "5") (pinfunction "INB+_5") (pintype "unspecified"))
      (node (ref "U23") (pin "3") (pinfunction "INA+_3") (pintype "unspecified"))
      (node (ref "U23") (pin "5") (pinfunction "INB+_5") (pintype "unspecified"))
    )
    (net (code "195") (name "unconnected-(J2-Pad1)") (class "Default")
      (node (ref "J2") (pin "1") (pinfunction "1_1") (pintype "unspecified"))
    )
    (net (code "196") (name "unconnected-(J2-Pad3)") (class "Default")
      (node (ref "J2") (pin "3") (pinfunction "3_3") (pintype "unspecified+no_connect"))
    )
    (net (code "197") (name "unconnected-(J2-Pad6)") (class "Default")
      (node (ref "J2") (pin "6") (pinfunction "6_6") (pintype "unspecified+no_connect"))
    )
    (net (code "198") (name "unconnected-(J2-Pad7)") (class "Default")
      (node (ref "J2") (pin "7") (pinfunction "7_7") (pintype "unspecified+no_connect"))
    )
    (net (code "199") (name "unconnected-(J3-Pad1)") (class "Default")
      (node (ref "J3") (pin "1") (pinfunction "1_1") (pintype "unspecified+no_connect"))
    )
    (net (code "200") (name "unconnected-(J3-Pad3)") (class "Default")
      (node (ref "J3") (pin "3") (pinfunction "3_3") (pintype "unspecified+no_connect"))
    )
    (net (code "201") (name "unconnected-(J3-Pad6)") (class "Default")
      (node (ref "J3") (pin "6") (pinfunction "6_6") (pintype "unspecified+no_connect"))
    )
    (net (code "202") (name "unconnected-(J3-Pad7)") (class "Default")
      (node (ref "J3") (pin "7") (pinfunction "7_7") (pintype "unspecified+no_connect"))
    )
    (net (code "203") (name "unconnected-(U1-ON{slash}OFF-PadON-OFF)") (class "Default")
      (node (ref "U1") (pin "ON-OFF") (pinfunction "ON/OFF_ON-OFF") (pintype "bidirectional+no_connect"))
    )
    (net (code "204") (name "unconnected-(U1-PROGRAM-PadPGM)") (class "Default")
      (node (ref "U1") (pin "PGM") (pinfunction "PROGRAM_PGM") (pintype "bidirectional+no_connect"))
    )
    (net (code "205") (name "unconnected-(U1-Pad12)") (class "Default")
      (node (ref "U1") (pin "12") (pinfunction "12_12") (pintype "bidirectional+no_connect"))
    )
    (net (code "206") (name "unconnected-(U1-Pad13)") (class "Default")
      (node (ref "U1") (pin "13") (pinfunction "13_13") (pintype "bidirectional+no_connect"))
    )
    (net (code "207") (name "unconnected-(U1-PadVBAT)") (class "Default")
      (node (ref "U1") (pin "VBAT") (pinfunction "VBAT_VBAT") (pintype "unspecified+no_connect"))
    )
    (net (code "208") (name "unconnected-(U5-NC-Pad1)") (class "Default")
      (node (ref "U5") (pin "1") (pinfunction "NC_1") (pintype "unspecified+no_connect"))
    )
    (net (code "209") (name "unconnected-(U5-NC-Pad4)") (class "Default")
      (node (ref "U5") (pin "4") (pinfunction "NC_4") (pintype "unspecified+no_connect"))
    )
  )
)
